# FPGA_IO.net
KiCad netlist of a schematic drawn in Altium Designer
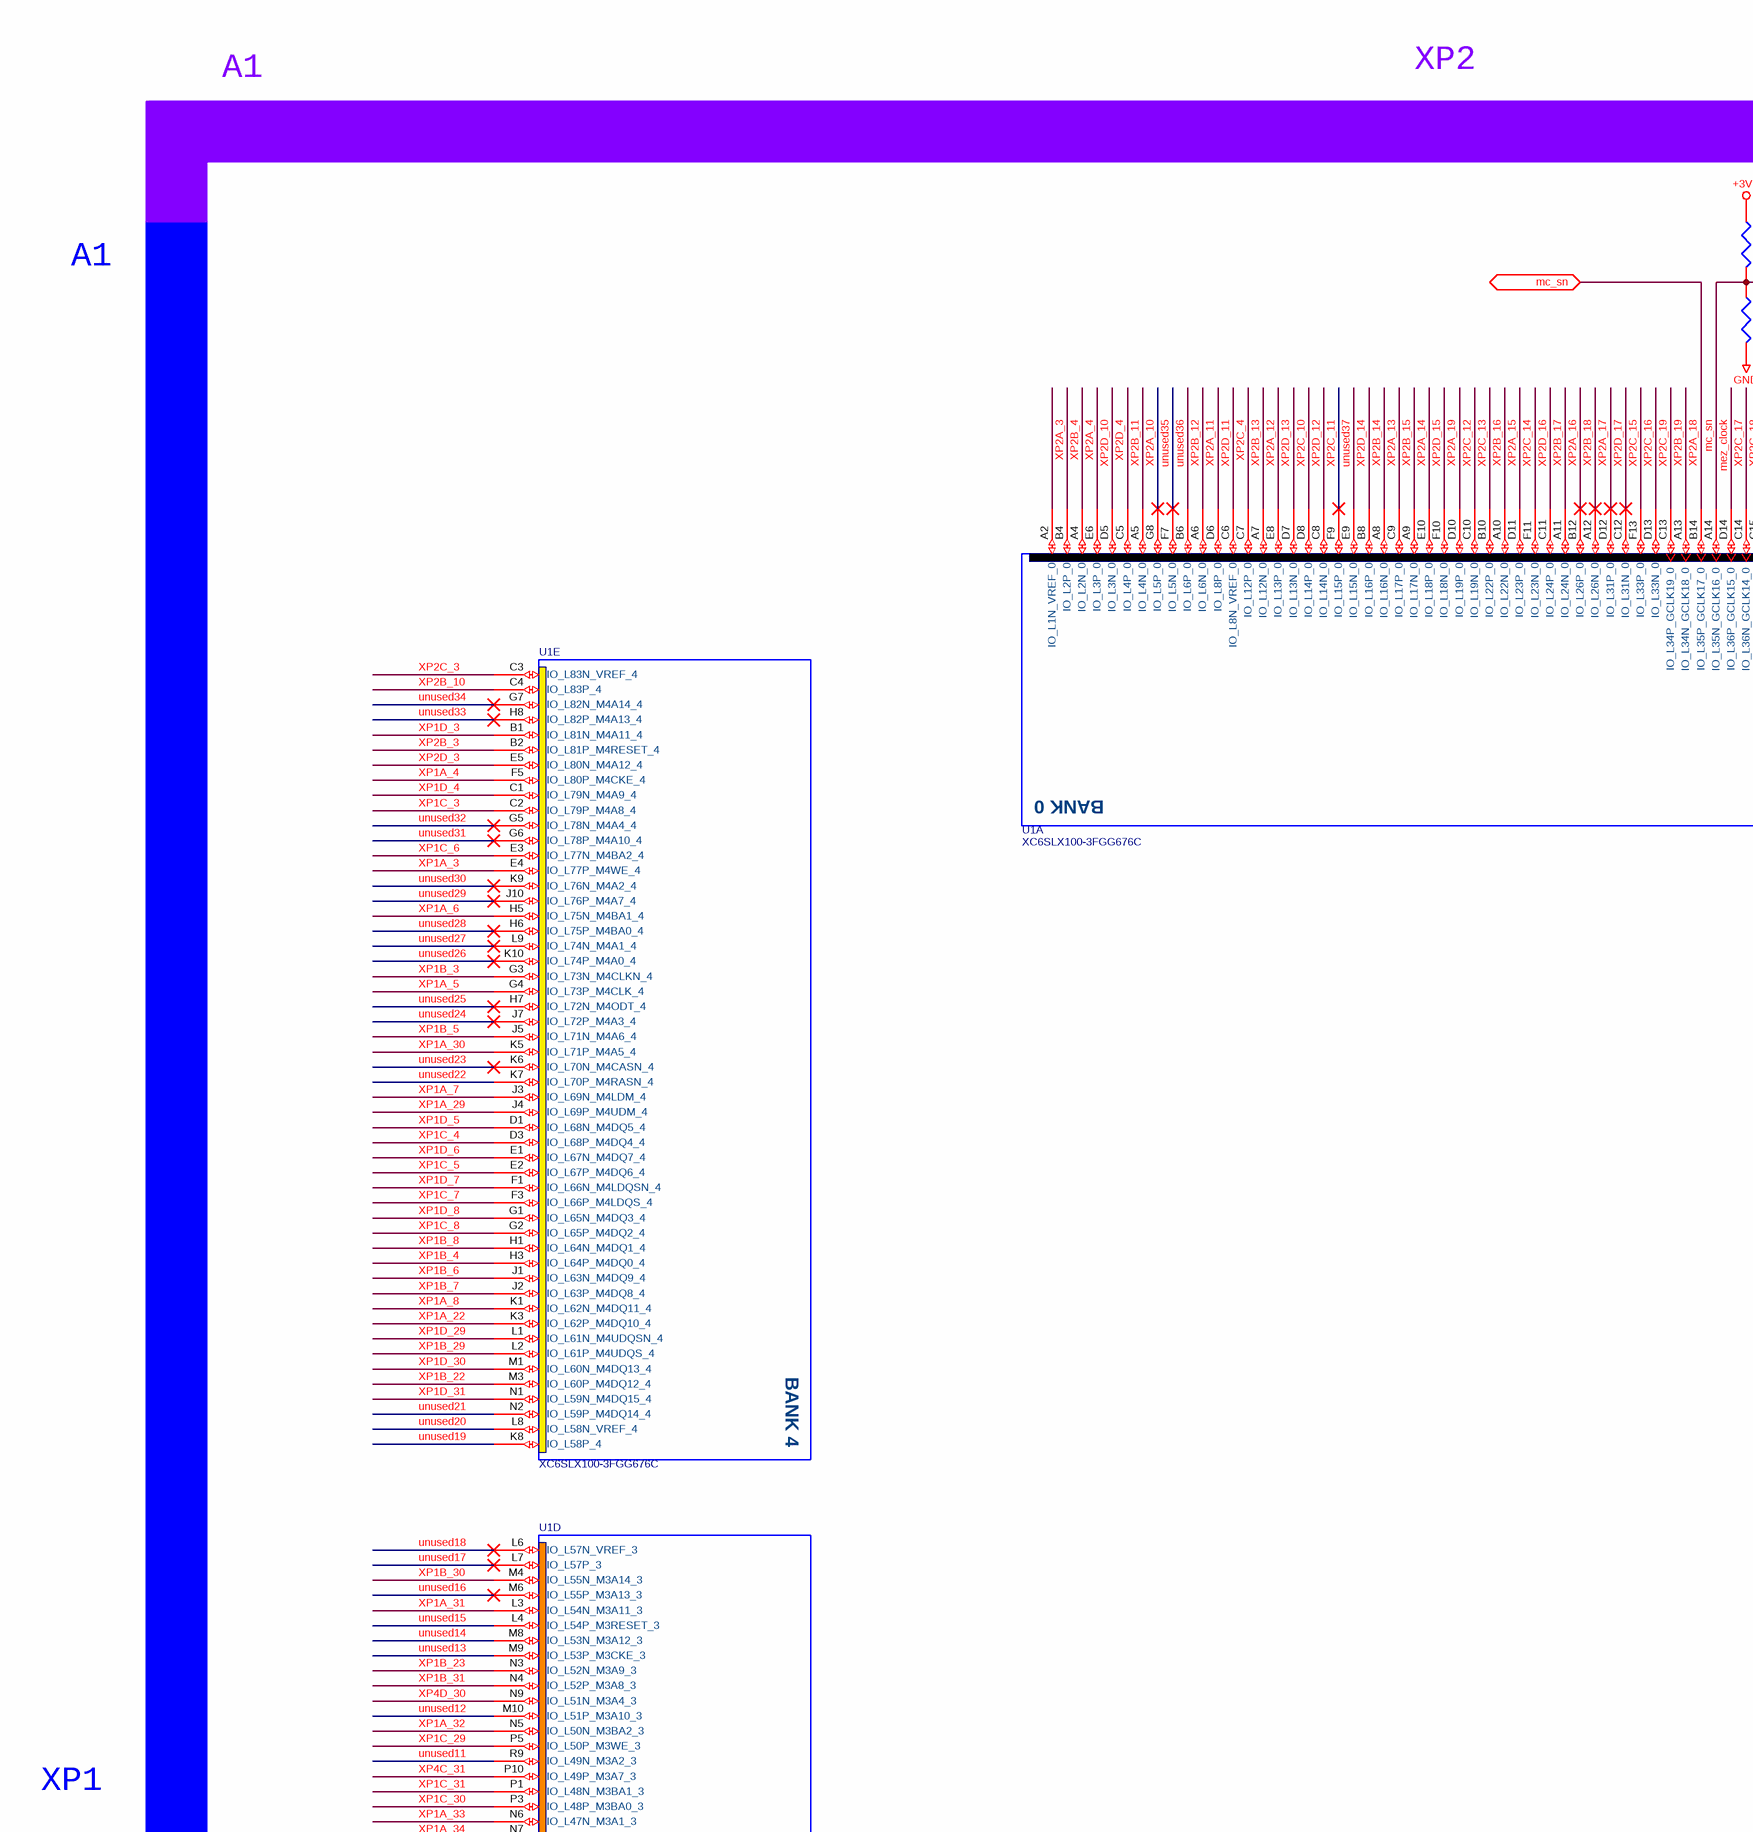
[diagram p0: FPGA_IO.SchDoc, top left]
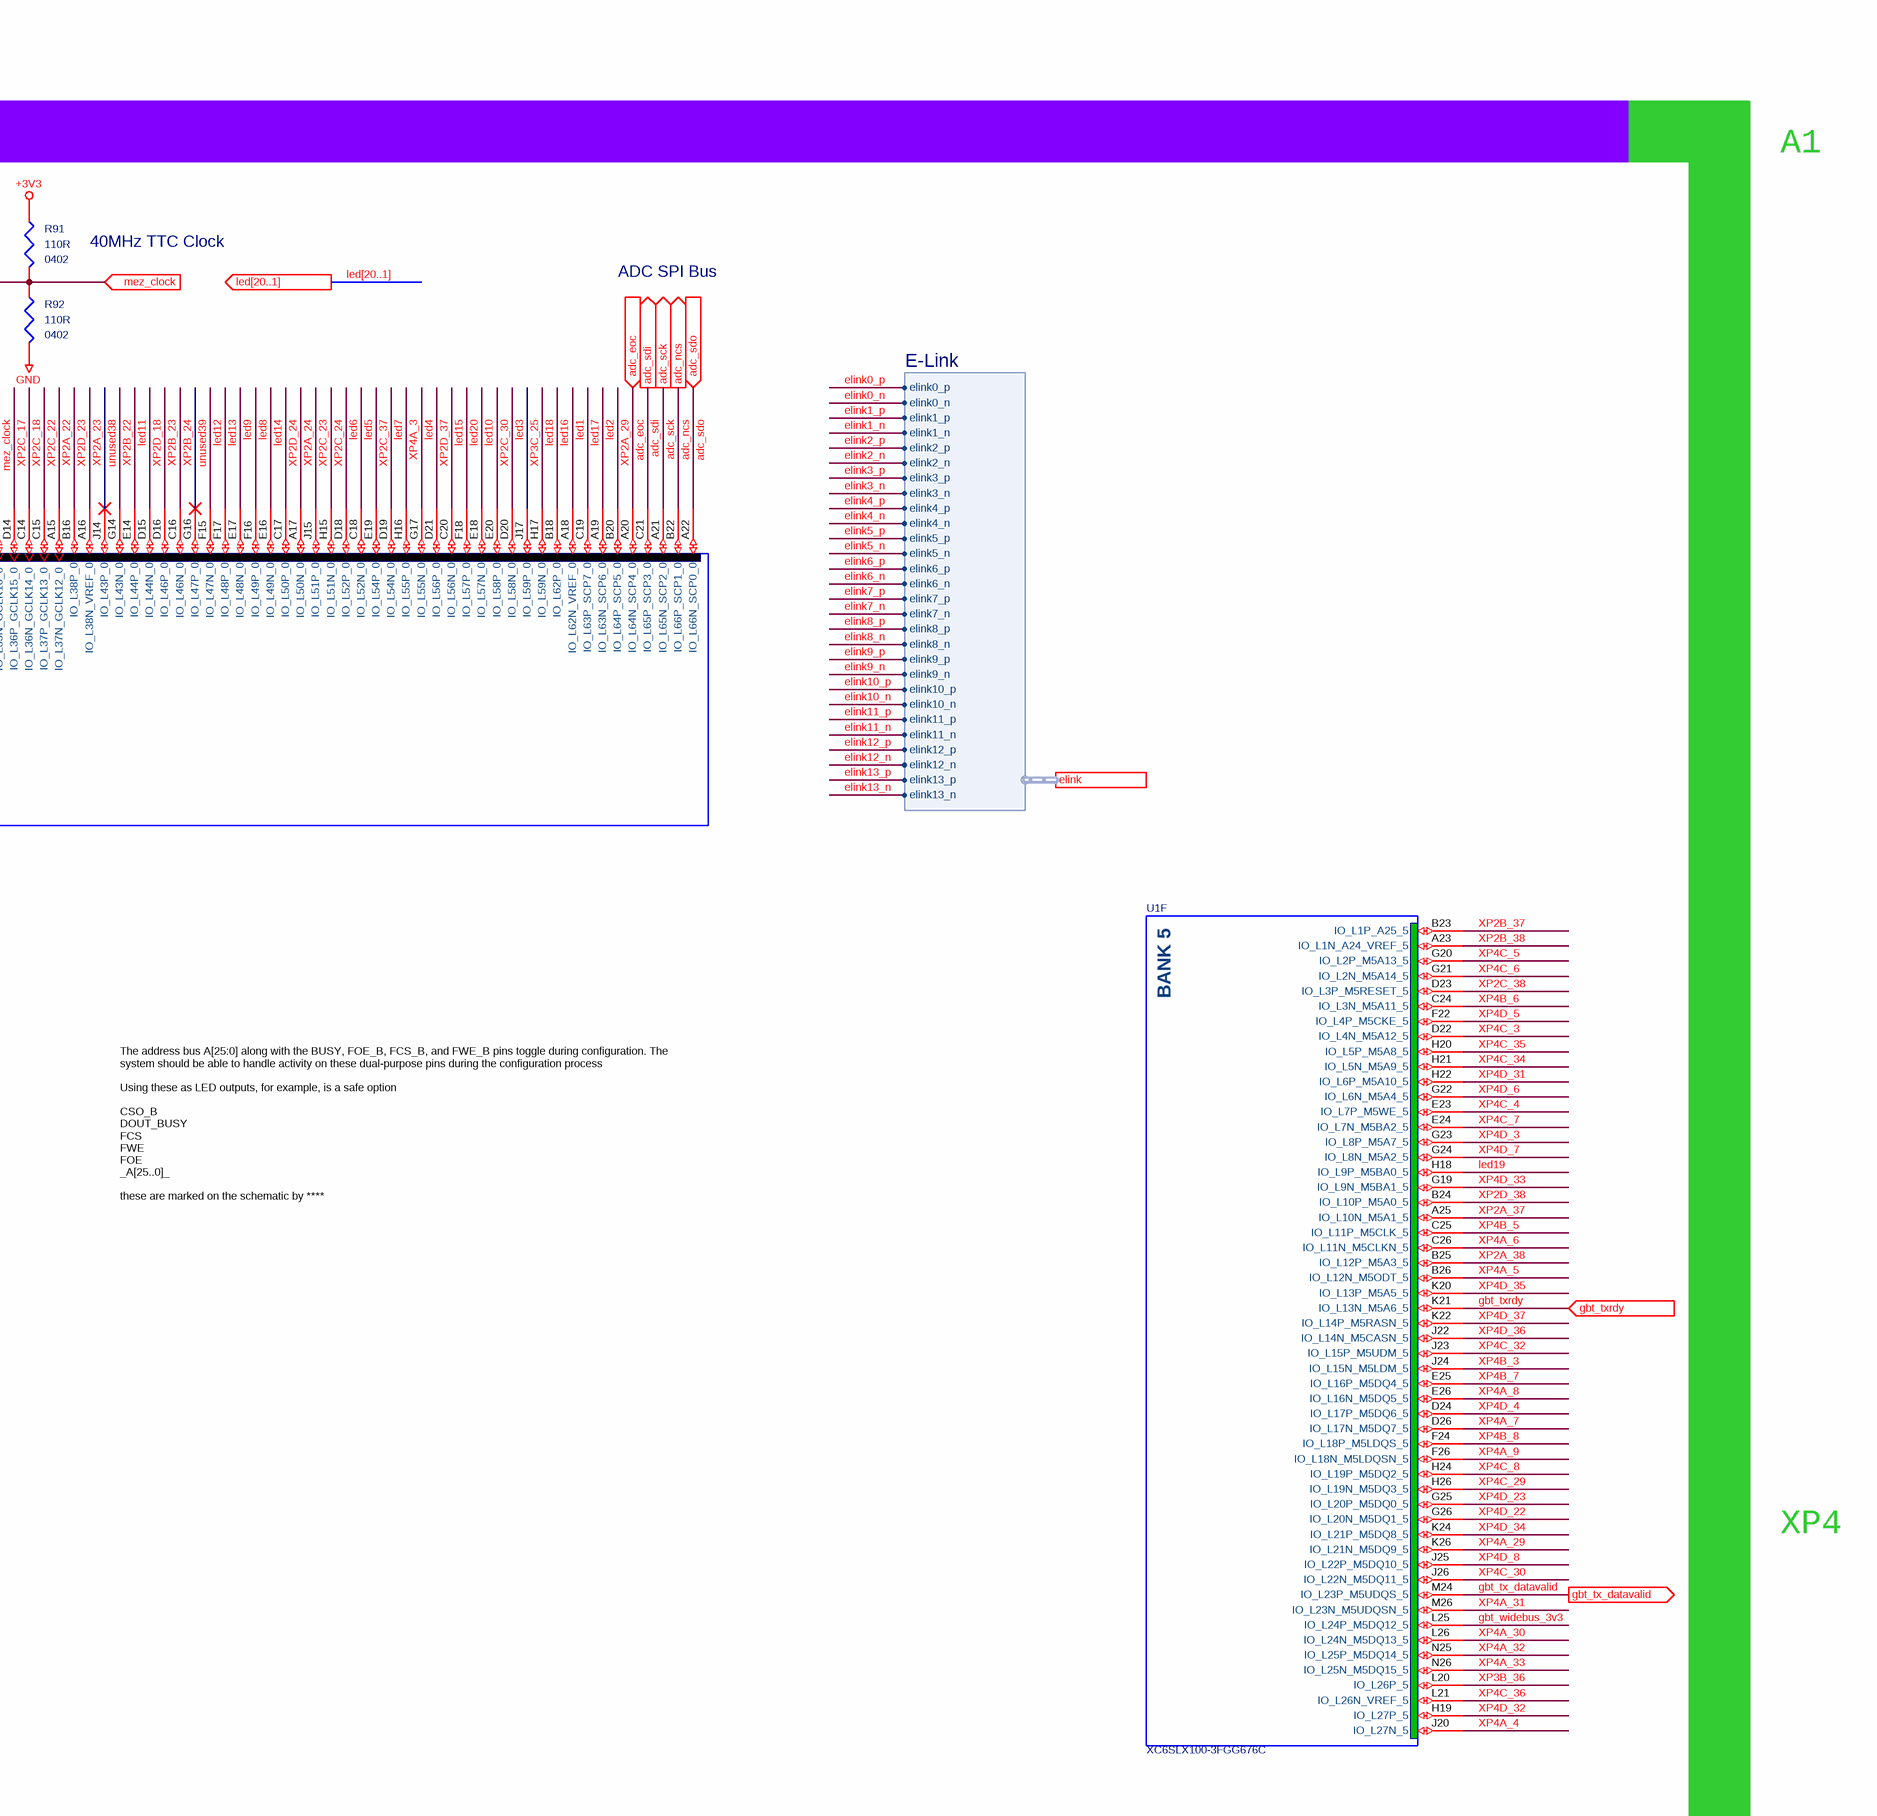
[diagram p1: FPGA_IO.SchDoc, top right]
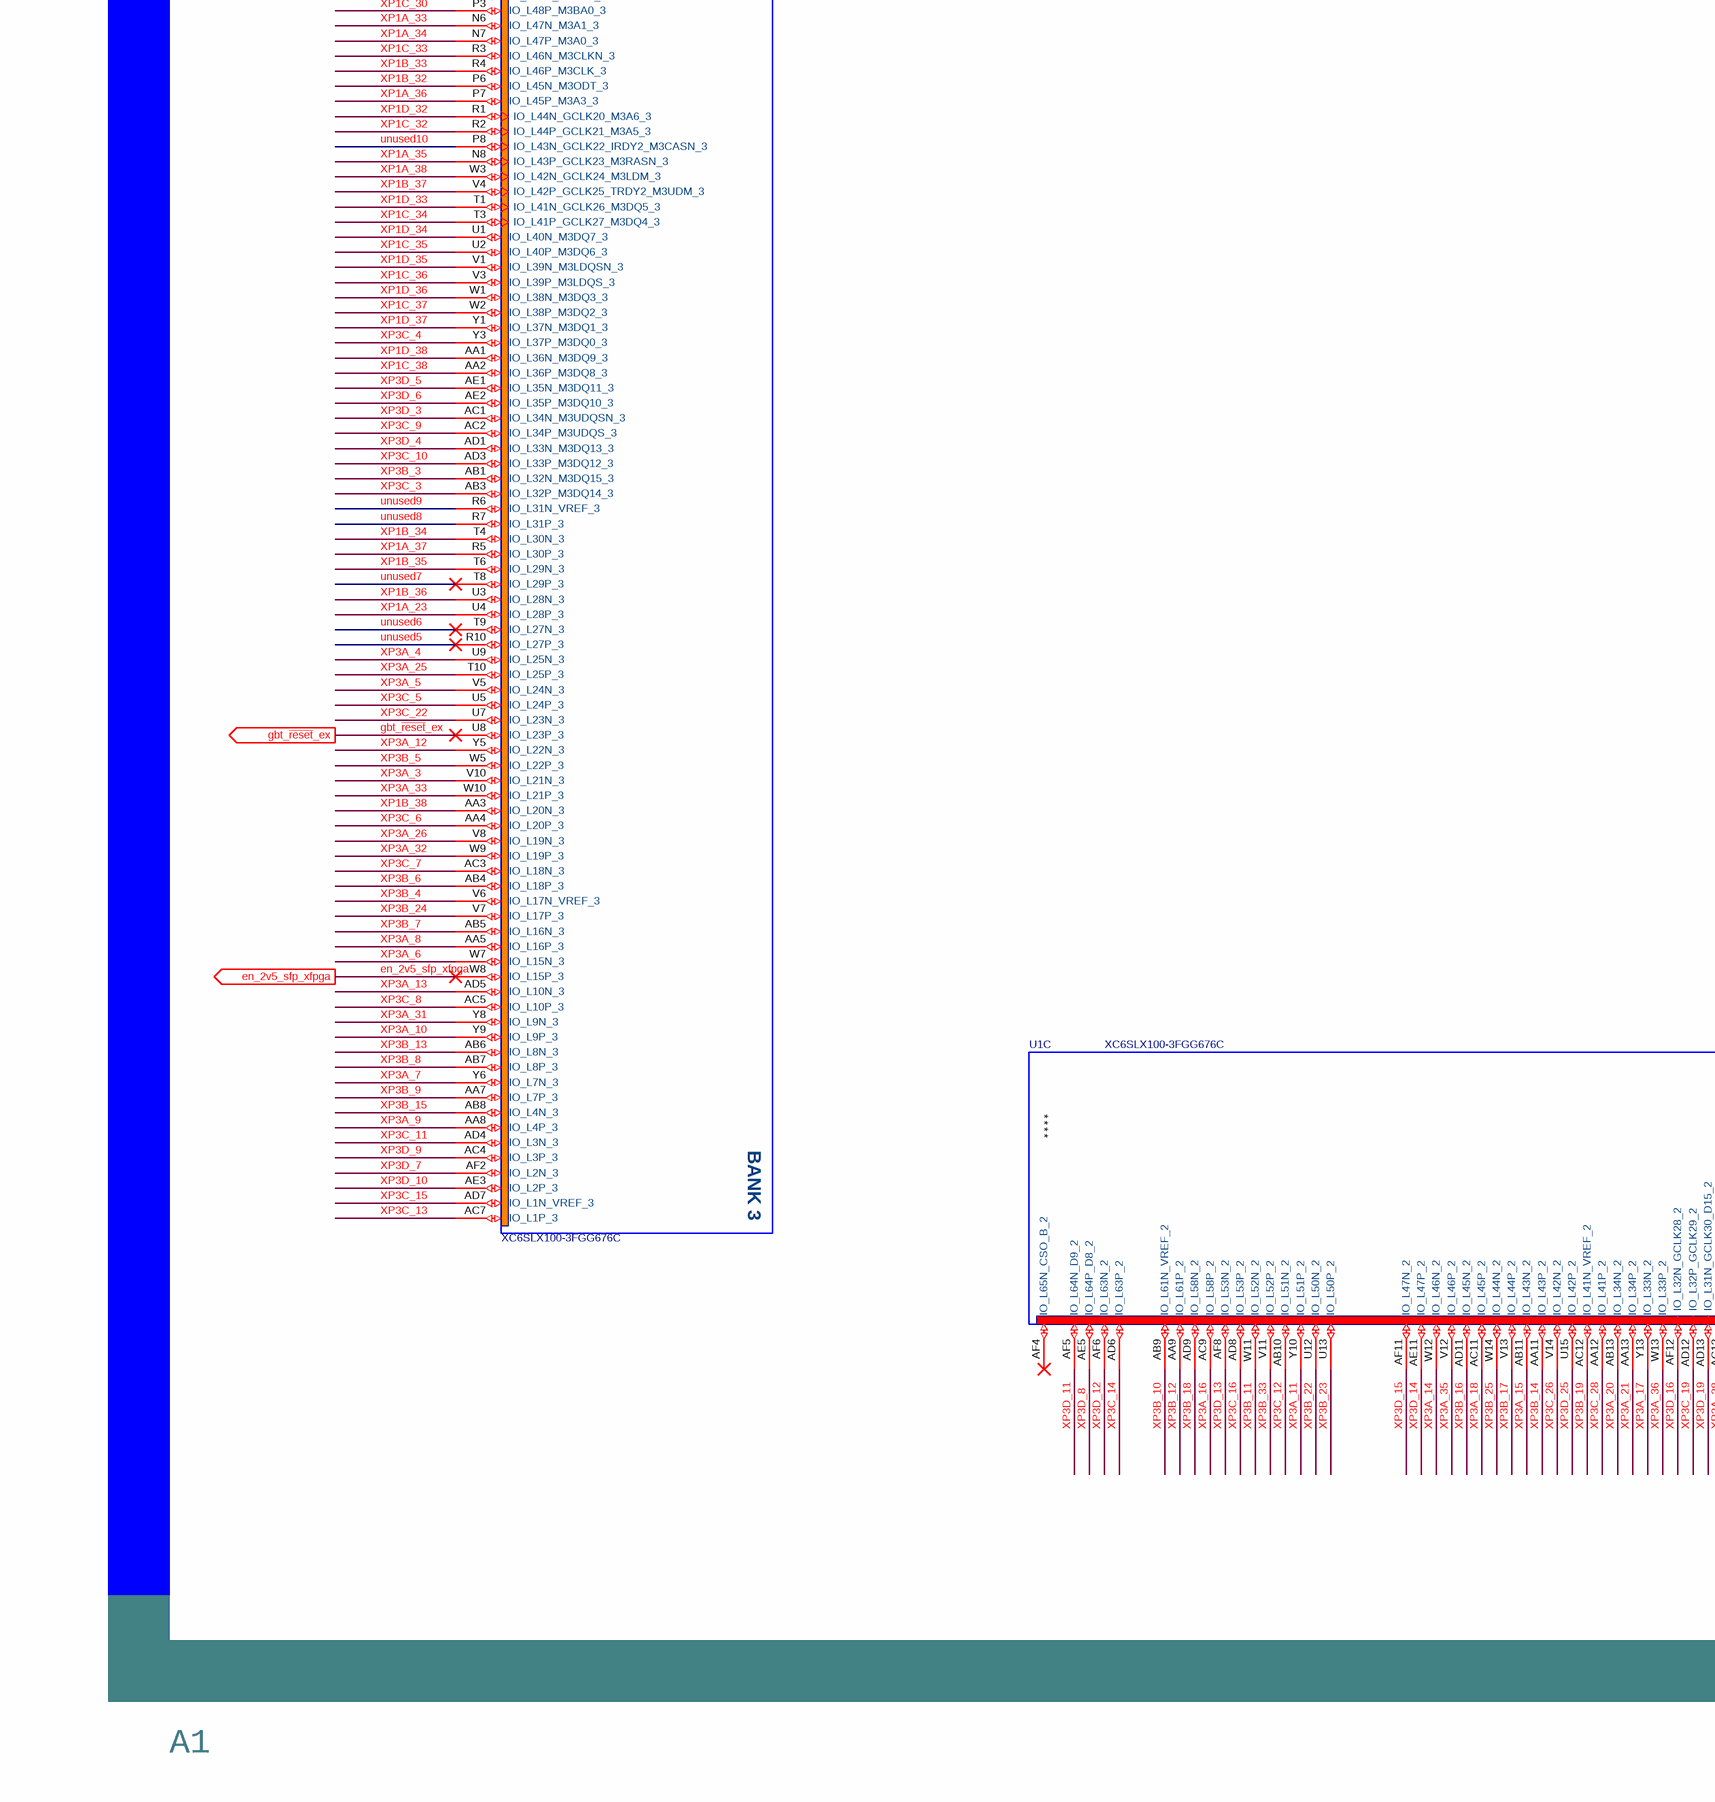
[diagram p2: FPGA_IO.SchDoc, bottom left]
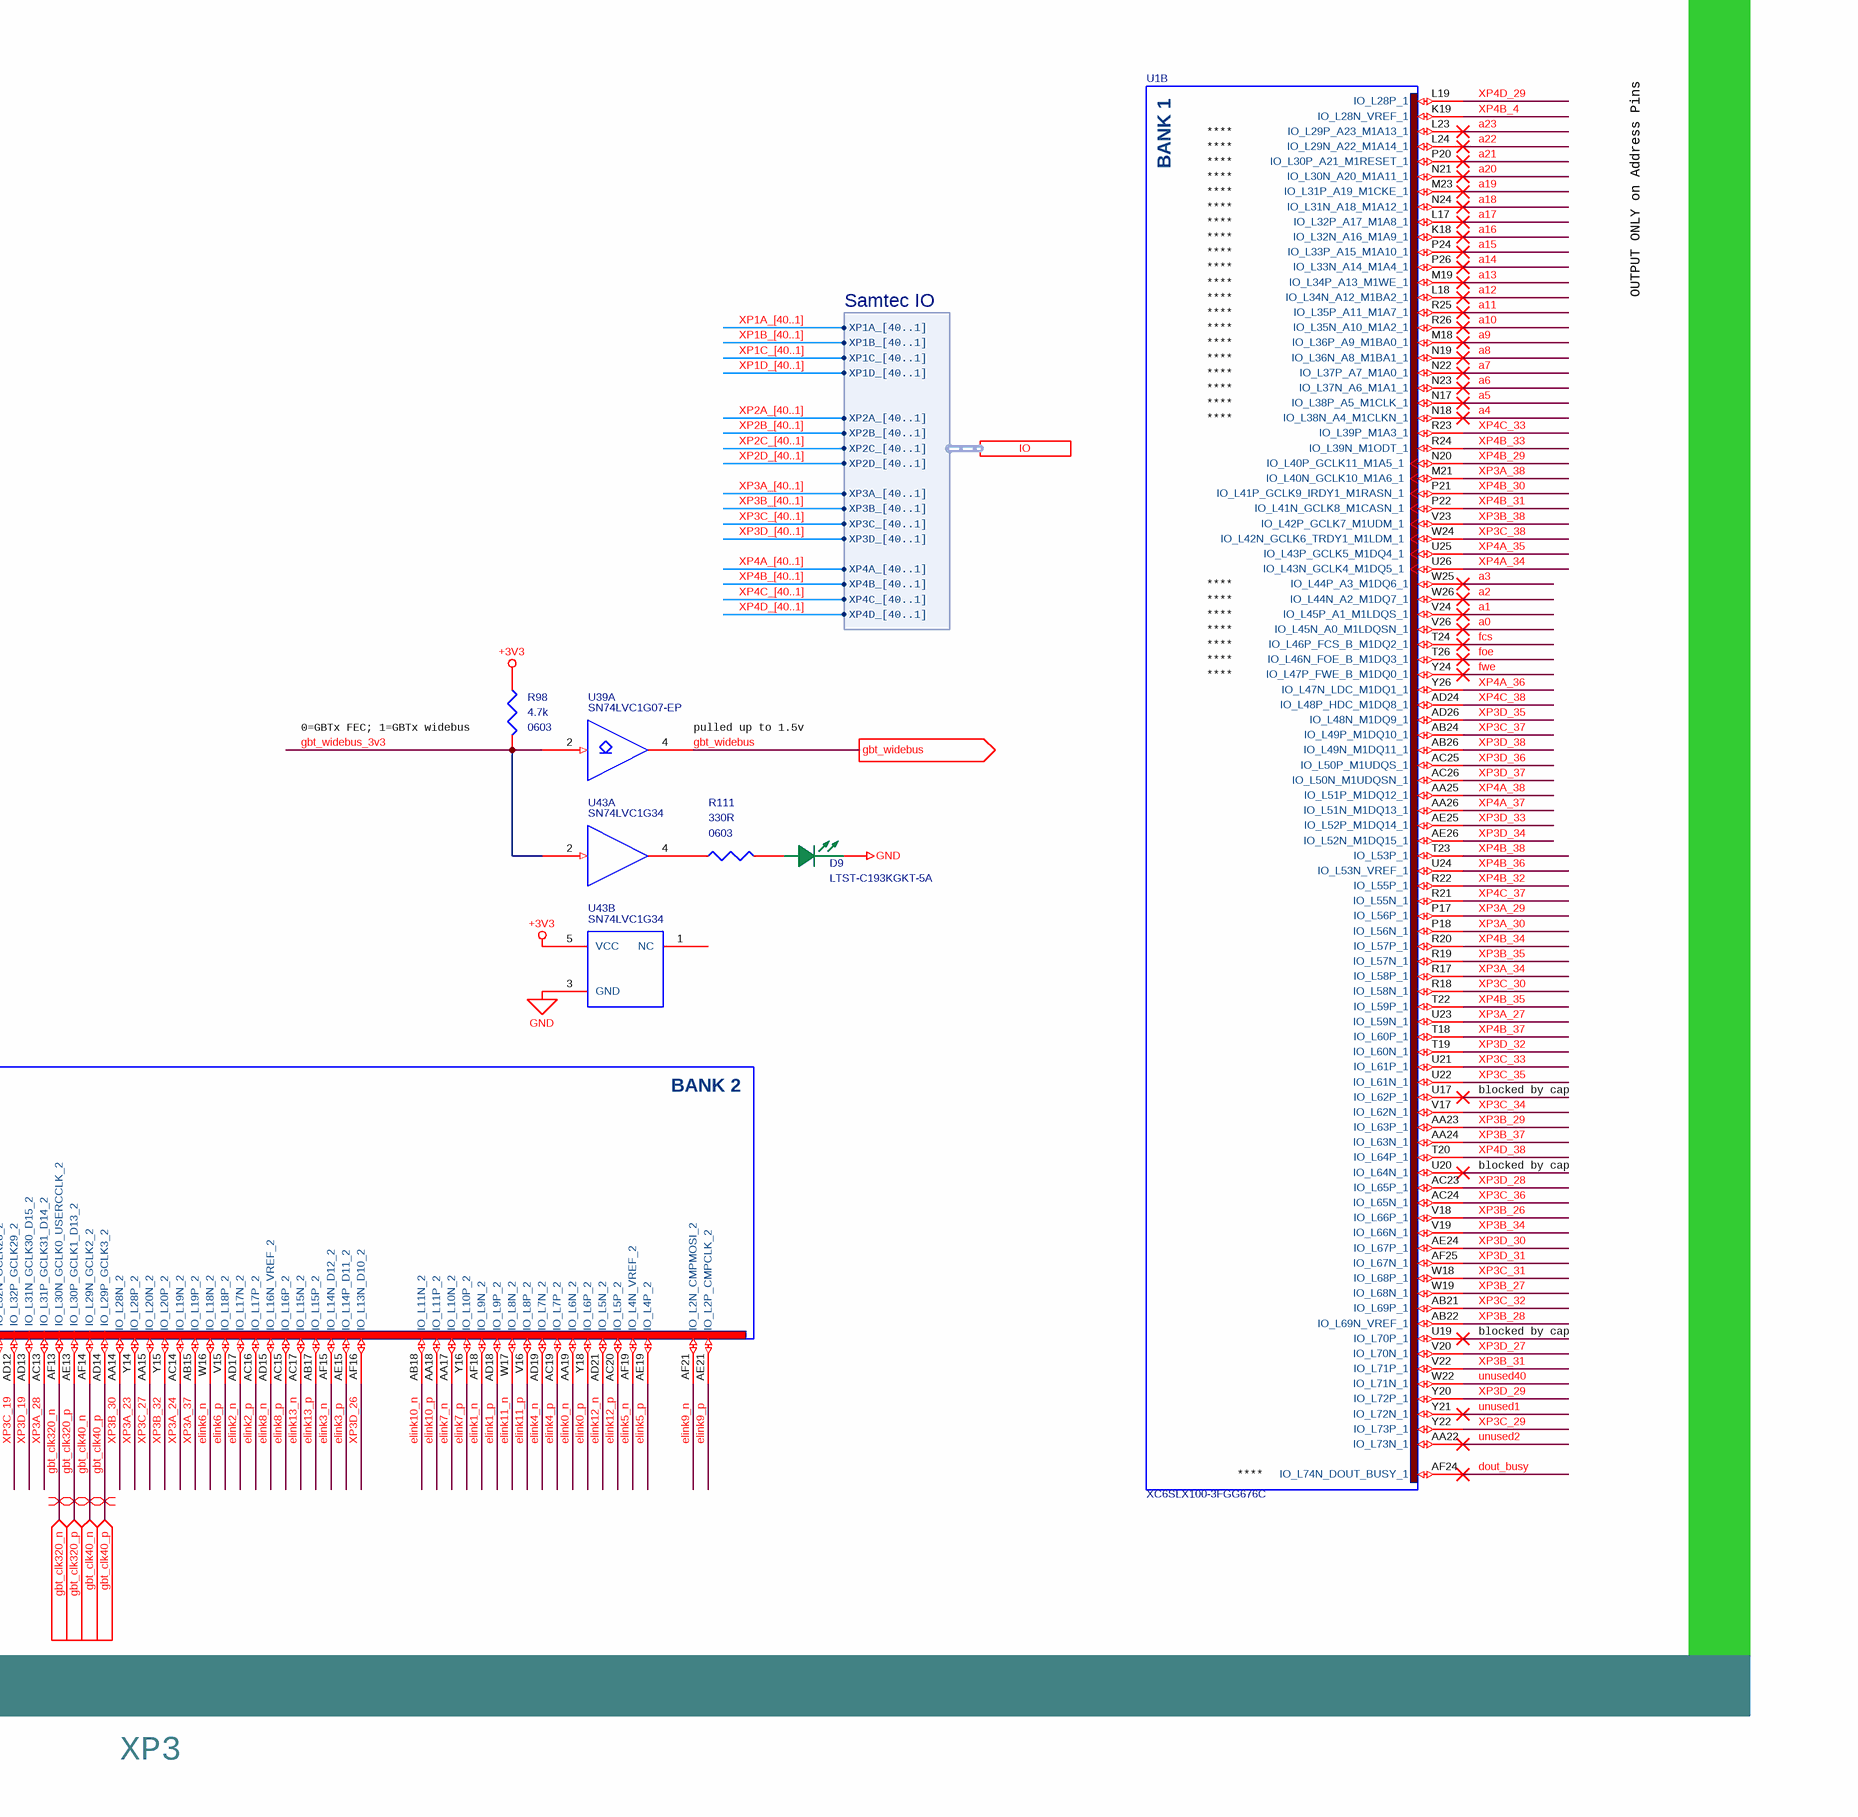
[diagram p3: FPGA_IO.SchDoc, bottom right]

(export (version "E")
  (design (tool "Eeschema 10.0.6"))
  (components
    (comp (ref "D9")
      (value "LTST-C193KGKT-5A")
      (footprint "MC_S6/SM/LED_0603")
      (description "LED GREEN CLEAR 0603 SMD")
      (fields (field (name "MANUFACTURER") "Lite-On Inc."))
      (libsource (lib "ALCT_MEZ_SPARTAN6_Library") (part "LTST-C193KGKT-5A"))
    )
    (comp (ref "R91")
      (value "110R")
      (footprint "MC_S6/SM/R_0402_IPC")
      (description "RES SMD 110 OHM 1% 1/10W 0402")
      (fields
        (field (name "MANUFACTURER") "Panasonic Electronic Components")
        (field (name "MANUFACTURER PART NUMBER") "ERJ-2RKF1100X")
        (field (name "SUPPLIER DEVICE PACKAGE") "0402")
      )
      (libsource (lib "ALCT_MEZ_SPARTAN6_Library") (part "ERJ-2RKF1100X"))
    )
    (comp (ref "R92")
      (value "110R")
      (footprint "MC_S6/SM/R_0402_IPC")
      (description "RES SMD 110 OHM 1% 1/10W 0402")
      (fields
        (field (name "MANUFACTURER") "Panasonic Electronic Components")
        (field (name "MANUFACTURER PART NUMBER") "ERJ-2RKF1100X")
        (field (name "SUPPLIER DEVICE PACKAGE") "0402")
      )
      (libsource (lib "ALCT_MEZ_SPARTAN6_Library") (part "ERJ-2RKF1100X"))
    )
    (comp (ref "R98")
      (value "4.7k")
      (footprint "MC_S6/SM/R_0603_IPC")
      (description "RES SMD 4.7K OHM 1% 1/10W 0603")
      (fields
        (field (name "TOLERANCE") "±1%")
        (field (name "MANUFACTURER") "Bourns Inc.")
        (field (name "SUPPLIER DEVICE PACKAGE") "0603")
      )
      (libsource (lib "ALCT_MEZ_SPARTAN6_Library") (part "CR0603-FX-4701ELF"))
    )
    (comp (ref "R111")
      (value "330R")
      (footprint "MC_S6/SM/R_0603_IPC")
      (description "RES SMD 330 OHM 1% 1/10W 0603")
      (fields
        (field (name "MANUFACTURER") "Bourns Inc.")
        (field (name "MANUFACTURER PART NUMBER") "CR0603-FX-3300ELF")
        (field (name "SUPPLIER DEVICE PACKAGE") "0603")
      )
      (libsource (lib "ALCT_MEZ_SPARTAN6_Library") (part "CR0603-FX-3300ELF"))
    )
    (comp (ref "U1")
      (value "XC6SLX100-3FGG676C")
      (footprint "FGG676")
      (fields (field (name "MANUFACTURER") "Xilinx Inc."))
      (libsource (lib "ALCT_MEZ_SPARTAN6_Library") (part "XC6SLX100-3FGG676C"))
    )
    (comp (ref "U39")
      (value "SN74LVC1G07-EP")
      (footprint "SOT353-1")
      (description "IC BUFF/DVR NON-INVERT Open Drain SC70-5")
      (fields
        (field (name "MANUFACTURER") "Texas Instruments")
        (field (name "MANUFACTURER PART NUMBER") "SN74LVC1G07MDCKREP")
      )
      (libsource (lib "ALCT_MEZ_SPARTAN6_Library") (part "SN74LVC1G07-EP"))
    )
    (comp (ref "U43")
      (value "SN74LVC1G34")
      (footprint "MC_S6/SM/SOT_553_DRL5")
      (description "IC BUFFER NON-INVERT SOT5")
      (fields
        (field (name "MANUFACTURER") "Texas Instruments")
        (field (name "MANUFACTURER PART NUMBER") "SN74LVC1G34DRLR")
      )
      (libsource (lib "ALCT_MEZ_SPARTAN6_Library") (part "SN74LVC1G34DRLR"))
    )
  )
  (nets
    (net (code "292") (name "+3V3") (class "Default")
      (node (ref "R91") (pin "1") (pinfunction "1_1") (pintype "passive"))
      (node (ref "R98") (pin "1") (pinfunction "1_1") (pintype "passive"))
      (node (ref "U43") (pin "5") (pinfunction "VCC_5") (pintype "power_in"))
    )
    (net (code "294") (name "/XP1A_3") (class "Default")
      (node (ref "U1") (pin "E4") (pinfunction "IO_L77P_M4WE_4_E4") (pintype "bidirectional"))
    )
    (net (code "295") (name "/XP1A_4") (class "Default")
      (node (ref "U1") (pin "F5") (pinfunction "IO_L80P_M4CKE_4_F5") (pintype "bidirectional"))
    )
    (net (code "296") (name "/XP1A_5") (class "Default")
      (node (ref "U1") (pin "G4") (pinfunction "IO_L73P_M4CLK_4_G4") (pintype "bidirectional"))
    )
    (net (code "297") (name "/XP1A_6") (class "Default")
      (node (ref "U1") (pin "H5") (pinfunction "IO_L75N_M4BA1_4_H5") (pintype "bidirectional"))
    )
    (net (code "298") (name "/XP1A_7") (class "Default")
      (node (ref "U1") (pin "J3") (pinfunction "IO_L69N_M4LDM_4_J3") (pintype "bidirectional"))
    )
    (net (code "299") (name "/XP1A_8") (class "Default")
      (node (ref "U1") (pin "K1") (pinfunction "IO_L62N_M4DQ11_4_K1") (pintype "bidirectional"))
    )
    (net (code "300") (name "/XP1A_22") (class "Default")
      (node (ref "U1") (pin "K3") (pinfunction "IO_L62P_M4DQ10_4_K3") (pintype "bidirectional"))
    )
    (net (code "301") (name "/XP1A_23") (class "Default")
      (node (ref "U1") (pin "U4") (pinfunction "IO_L28P_3_U4") (pintype "bidirectional"))
    )
    (net (code "302") (name "/XP1A_29") (class "Default")
      (node (ref "U1") (pin "J4") (pinfunction "IO_L69P_M4UDM_4_J4") (pintype "bidirectional"))
    )
    (net (code "303") (name "/XP1A_30") (class "Default")
      (node (ref "U1") (pin "K5") (pinfunction "IO_L71P_M4A5_4_K5") (pintype "bidirectional"))
    )
    (net (code "304") (name "/XP1A_31") (class "Default")
      (node (ref "U1") (pin "L3") (pinfunction "IO_L54N_M3A11_3_L3") (pintype "bidirectional"))
    )
    (net (code "305") (name "/XP1A_32") (class "Default")
      (node (ref "U1") (pin "N5") (pinfunction "IO_L50N_M3BA2_3_N5") (pintype "bidirectional"))
    )
    (net (code "306") (name "/XP1A_33") (class "Default")
      (node (ref "U1") (pin "N6") (pinfunction "IO_L47N_M3A1_3_N6") (pintype "bidirectional"))
    )
    (net (code "307") (name "/XP1A_34") (class "Default")
      (node (ref "U1") (pin "N7") (pinfunction "IO_L47P_M3A0_3_N7") (pintype "bidirectional"))
    )
    (net (code "308") (name "/XP1A_35") (class "Default")
      (node (ref "U1") (pin "N8") (pinfunction "IO_L43P_GCLK23_M3RASN_3_N8") (pintype "bidirectional"))
    )
    (net (code "309") (name "/XP1A_36") (class "Default")
      (node (ref "U1") (pin "P7") (pinfunction "IO_L45P_M3A3_3_P7") (pintype "bidirectional"))
    )
    (net (code "310") (name "/XP1A_37") (class "Default")
      (node (ref "U1") (pin "R5") (pinfunction "IO_L30P_3_R5") (pintype "bidirectional"))
    )
    (net (code "311") (name "/XP1A_38") (class "Default")
      (node (ref "U1") (pin "W3") (pinfunction "IO_L42N_GCLK24_M3LDM_3_W3") (pintype "bidirectional"))
    )
    (net (code "313") (name "/XP1B_3") (class "Default")
      (node (ref "U1") (pin "G3") (pinfunction "IO_L73N_M4CLKN_4_G3") (pintype "bidirectional"))
    )
    (net (code "314") (name "/XP1B_4") (class "Default")
      (node (ref "U1") (pin "H3") (pinfunction "IO_L64P_M4DQ0_4_H3") (pintype "bidirectional"))
    )
    (net (code "315") (name "/XP1B_5") (class "Default")
      (node (ref "U1") (pin "J5") (pinfunction "IO_L71N_M4A6_4_J5") (pintype "bidirectional"))
    )
    (net (code "316") (name "/XP1B_6") (class "Default")
      (node (ref "U1") (pin "J1") (pinfunction "IO_L63N_M4DQ9_4_J1") (pintype "bidirectional"))
    )
    (net (code "317") (name "/XP1B_7") (class "Default")
      (node (ref "U1") (pin "J2") (pinfunction "IO_L63P_M4DQ8_4_J2") (pintype "bidirectional"))
    )
    (net (code "318") (name "/XP1B_8") (class "Default")
      (node (ref "U1") (pin "H1") (pinfunction "IO_L64N_M4DQ1_4_H1") (pintype "bidirectional"))
    )
    (net (code "319") (name "/XP1B_22") (class "Default")
      (node (ref "U1") (pin "M3") (pinfunction "IO_L60P_M4DQ12_4_M3") (pintype "bidirectional"))
    )
    (net (code "320") (name "/XP1B_23") (class "Default")
      (node (ref "U1") (pin "N3") (pinfunction "IO_L52N_M3A9_3_N3") (pintype "bidirectional"))
    )
    (net (code "321") (name "/XP1B_29") (class "Default")
      (node (ref "U1") (pin "L2") (pinfunction "IO_L61P_M4UDQS_4_L2") (pintype "bidirectional"))
    )
    (net (code "322") (name "/XP1B_30") (class "Default")
      (node (ref "U1") (pin "M4") (pinfunction "IO_L55N_M3A14_3_M4") (pintype "bidirectional"))
    )
    (net (code "323") (name "/XP1B_31") (class "Default")
      (node (ref "U1") (pin "N4") (pinfunction "IO_L52P_M3A8_3_N4") (pintype "bidirectional"))
    )
    (net (code "324") (name "/XP1B_32") (class "Default")
      (node (ref "U1") (pin "P6") (pinfunction "IO_L45N_M3ODT_3_P6") (pintype "bidirectional"))
    )
    (net (code "325") (name "/XP1B_33") (class "Default")
      (node (ref "U1") (pin "R4") (pinfunction "IO_L46P_M3CLK_3_R4") (pintype "bidirectional"))
    )
    (net (code "326") (name "/XP1B_34") (class "Default")
      (node (ref "U1") (pin "T4") (pinfunction "IO_L30N_3_T4") (pintype "bidirectional"))
    )
    (net (code "327") (name "/XP1B_35") (class "Default")
      (node (ref "U1") (pin "T6") (pinfunction "IO_L29N_3_T6") (pintype "bidirectional"))
    )
    (net (code "328") (name "/XP1B_36") (class "Default")
      (node (ref "U1") (pin "U3") (pinfunction "IO_L28N_3_U3") (pintype "bidirectional"))
    )
    (net (code "329") (name "/XP1B_37") (class "Default")
      (node (ref "U1") (pin "V4") (pinfunction "IO_L42P_GCLK25_TRDY2_M3UDM_3_V4") (pintype "bidirectional"))
    )
    (net (code "330") (name "/XP1B_38") (class "Default")
      (node (ref "U1") (pin "AA3") (pinfunction "IO_L20N_3_AA3") (pintype "bidirectional"))
    )
    (net (code "332") (name "/XP1C_3") (class "Default")
      (node (ref "U1") (pin "C2") (pinfunction "IO_L79P_M4A8_4_C2") (pintype "bidirectional"))
    )
    (net (code "333") (name "/XP1C_4") (class "Default")
      (node (ref "U1") (pin "D3") (pinfunction "IO_L68P_M4DQ4_4_D3") (pintype "bidirectional"))
    )
    (net (code "334") (name "/XP1C_5") (class "Default")
      (node (ref "U1") (pin "E2") (pinfunction "IO_L67P_M4DQ6_4_E2") (pintype "bidirectional"))
    )
    (net (code "335") (name "/XP1C_6") (class "Default")
      (node (ref "U1") (pin "E3") (pinfunction "IO_L77N_M4BA2_4_E3") (pintype "bidirectional"))
    )
    (net (code "336") (name "/XP1C_7") (class "Default")
      (node (ref "U1") (pin "F3") (pinfunction "IO_L66P_M4LDQS_4_F3") (pintype "bidirectional"))
    )
    (net (code "337") (name "/XP1C_8") (class "Default")
      (node (ref "U1") (pin "G2") (pinfunction "IO_L65P_M4DQ2_4_G2") (pintype "bidirectional"))
    )
    (net (code "338") (name "/XP1C_29") (class "Default")
      (node (ref "U1") (pin "P5") (pinfunction "IO_L50P_M3WE_3_P5") (pintype "bidirectional"))
    )
    (net (code "339") (name "/XP1C_30") (class "Default")
      (node (ref "U1") (pin "P3") (pinfunction "IO_L48P_M3BA0_3_P3") (pintype "bidirectional"))
    )
    (net (code "340") (name "/XP1C_31") (class "Default")
      (node (ref "U1") (pin "P1") (pinfunction "IO_L48N_M3BA1_3_P1") (pintype "bidirectional"))
    )
    (net (code "341") (name "/XP1C_32") (class "Default")
      (node (ref "U1") (pin "R2") (pinfunction "IO_L44P_GCLK21_M3A5_3_R2") (pintype "bidirectional"))
    )
    (net (code "342") (name "/XP1C_33") (class "Default")
      (node (ref "U1") (pin "R3") (pinfunction "IO_L46N_M3CLKN_3_R3") (pintype "bidirectional"))
    )
    (net (code "343") (name "/XP1C_34") (class "Default")
      (node (ref "U1") (pin "T3") (pinfunction "IO_L41P_GCLK27_M3DQ4_3_T3") (pintype "bidirectional"))
    )
    (net (code "344") (name "/XP1C_35") (class "Default")
      (node (ref "U1") (pin "U2") (pinfunction "IO_L40P_M3DQ6_3_U2") (pintype "bidirectional"))
    )
    (net (code "345") (name "/XP1C_36") (class "Default")
      (node (ref "U1") (pin "V3") (pinfunction "IO_L39P_M3LDQS_3_V3") (pintype "bidirectional"))
    )
    (net (code "346") (name "/XP1C_37") (class "Default")
      (node (ref "U1") (pin "W2") (pinfunction "IO_L38P_M3DQ2_3_W2") (pintype "bidirectional"))
    )
    (net (code "347") (name "/XP1C_38") (class "Default")
      (node (ref "U1") (pin "AA2") (pinfunction "IO_L36P_M3DQ8_3_AA2") (pintype "bidirectional"))
    )
    (net (code "349") (name "/XP1D_3") (class "Default")
      (node (ref "U1") (pin "B1") (pinfunction "IO_L81N_M4A11_4_B1") (pintype "bidirectional"))
    )
    (net (code "350") (name "/XP1D_4") (class "Default")
      (node (ref "U1") (pin "C1") (pinfunction "IO_L79N_M4A9_4_C1") (pintype "bidirectional"))
    )
    (net (code "351") (name "/XP1D_5") (class "Default")
      (node (ref "U1") (pin "D1") (pinfunction "IO_L68N_M4DQ5_4_D1") (pintype "bidirectional"))
    )
    (net (code "352") (name "/XP1D_6") (class "Default")
      (node (ref "U1") (pin "E1") (pinfunction "IO_L67N_M4DQ7_4_E1") (pintype "bidirectional"))
    )
    (net (code "353") (name "/XP1D_7") (class "Default")
      (node (ref "U1") (pin "F1") (pinfunction "IO_L66N_M4LDQSN_4_F1") (pintype "bidirectional"))
    )
    (net (code "354") (name "/XP1D_8") (class "Default")
      (node (ref "U1") (pin "G1") (pinfunction "IO_L65N_M4DQ3_4_G1") (pintype "bidirectional"))
    )
    (net (code "355") (name "/XP1D_29") (class "Default")
      (node (ref "U1") (pin "L1") (pinfunction "IO_L61N_M4UDQSN_4_L1") (pintype "bidirectional"))
    )
    (net (code "356") (name "/XP1D_30") (class "Default")
      (node (ref "U1") (pin "M1") (pinfunction "IO_L60N_M4DQ13_4_M1") (pintype "bidirectional"))
    )
    (net (code "357") (name "/XP1D_31") (class "Default")
      (node (ref "U1") (pin "N1") (pinfunction "IO_L59N_M4DQ15_4_N1") (pintype "bidirectional"))
    )
    (net (code "358") (name "/XP1D_32") (class "Default")
      (node (ref "U1") (pin "R1") (pinfunction "IO_L44N_GCLK20_M3A6_3_R1") (pintype "bidirectional"))
    )
    (net (code "359") (name "/XP1D_33") (class "Default")
      (node (ref "U1") (pin "T1") (pinfunction "IO_L41N_GCLK26_M3DQ5_3_T1") (pintype "bidirectional"))
    )
    (net (code "360") (name "/XP1D_34") (class "Default")
      (node (ref "U1") (pin "U1") (pinfunction "IO_L40N_M3DQ7_3_U1") (pintype "bidirectional"))
    )
    (net (code "361") (name "/XP1D_35") (class "Default")
      (node (ref "U1") (pin "V1") (pinfunction "IO_L39N_M3LDQSN_3_V1") (pintype "bidirectional"))
    )
    (net (code "362") (name "/XP1D_36") (class "Default")
      (node (ref "U1") (pin "W1") (pinfunction "IO_L38N_M3DQ3_3_W1") (pintype "bidirectional"))
    )
    (net (code "363") (name "/XP1D_37") (class "Default")
      (node (ref "U1") (pin "Y1") (pinfunction "IO_L37N_M3DQ1_3_Y1") (pintype "bidirectional"))
    )
    (net (code "364") (name "/XP1D_38") (class "Default")
      (node (ref "U1") (pin "AA1") (pinfunction "IO_L36N_M3DQ9_3_AA1") (pintype "bidirectional"))
    )
    (net (code "366") (name "/XP2A_3") (class "Default")
      (node (ref "U1") (pin "A2") (pinfunction "IO_L1N_VREF_0_A2") (pintype "bidirectional"))
    )
    (net (code "367") (name "/XP2A_4") (class "Default")
      (node (ref "U1") (pin "A4") (pinfunction "IO_L2N_0_A4") (pintype "bidirectional"))
    )
    (net (code "368") (name "/XP2A_10") (class "Default")
      (node (ref "U1") (pin "A5") (pinfunction "IO_L4N_0_A5") (pintype "bidirectional"))
    )
    (net (code "369") (name "/XP2A_11") (class "Default")
      (node (ref "U1") (pin "A6") (pinfunction "IO_L6N_0_A6") (pintype "bidirectional"))
    )
    (net (code "370") (name "/XP2A_12") (class "Default")
      (node (ref "U1") (pin "A7") (pinfunction "IO_L12N_0_A7") (pintype "bidirectional"))
    )
    (net (code "371") (name "/XP2A_13") (class "Default")
      (node (ref "U1") (pin "A8") (pinfunction "IO_L16N_0_A8") (pintype "bidirectional"))
    )
    (net (code "372") (name "/XP2A_14") (class "Default")
      (node (ref "U1") (pin "A9") (pinfunction "IO_L17N_0_A9") (pintype "bidirectional"))
    )
    (net (code "373") (name "/XP2A_15") (class "Default")
      (node (ref "U1") (pin "A10") (pinfunction "IO_L22N_0_A10") (pintype "bidirectional"))
    )
    (net (code "374") (name "/XP2A_16") (class "Default")
      (node (ref "U1") (pin "A11") (pinfunction "IO_L24N_0_A11") (pintype "bidirectional"))
    )
    (net (code "375") (name "/XP2A_17") (class "Default")
      (node (ref "U1") (pin "A12") (pinfunction "IO_L26N_0_A12") (pintype "bidirectional+no_connect"))
    )
    (net (code "376") (name "/XP2A_18") (class "Default")
      (node (ref "U1") (pin "A13") (pinfunction "IO_L34N_GCLK18_0_A13") (pintype "bidirectional"))
    )
    (net (code "377") (name "/XP2A_19") (class "Default")
      (node (ref "U1") (pin "F10") (pinfunction "IO_L18N_0_F10") (pintype "bidirectional"))
    )
    (net (code "378") (name "/XP2A_22") (class "Default")
      (node (ref "U1") (pin "A15") (pinfunction "IO_L37N_GCLK12_0_A15") (pintype "bidirectional"))
    )
    (net (code "379") (name "/XP2A_23") (class "Default")
      (node (ref "U1") (pin "A16") (pinfunction "IO_L38N_VREF_0_A16") (pintype "bidirectional"))
    )
    (net (code "380") (name "/XP2A_24") (class "Default")
      (node (ref "U1") (pin "A17") (pinfunction "IO_L50N_0_A17") (pintype "bidirectional"))
    )
    (net (code "381") (name "/XP2A_29") (class "Default")
      (node (ref "U1") (pin "B20") (pinfunction "IO_L64P_SCP5_0_B20") (pintype "bidirectional"))
    )
    (net (code "382") (name "/XP2A_37") (class "Default")
      (node (ref "U1") (pin "A25") (pinfunction "IO_L10N_M5A1_5_A25") (pintype "bidirectional"))
    )
    (net (code "383") (name "/XP2A_38") (class "Default")
      (node (ref "U1") (pin "B25") (pinfunction "IO_L12P_M5A3_5_B25") (pintype "bidirectional"))
    )
    (net (code "385") (name "/XP2B_3") (class "Default")
      (node (ref "U1") (pin "B2") (pinfunction "IO_L81P_M4RESET_4_B2") (pintype "bidirectional"))
    )
    (net (code "386") (name "/XP2B_4") (class "Default")
      (node (ref "U1") (pin "B4") (pinfunction "IO_L2P_0_B4") (pintype "bidirectional"))
    )
    (net (code "387") (name "/XP2B_10") (class "Default")
      (node (ref "U1") (pin "C4") (pinfunction "IO_L83P_4_C4") (pintype "bidirectional"))
    )
    (net (code "388") (name "/XP2B_11") (class "Default")
      (node (ref "U1") (pin "C5") (pinfunction "IO_L4P_0_C5") (pintype "bidirectional"))
    )
    (net (code "389") (name "/XP2B_12") (class "Default")
      (node (ref "U1") (pin "B6") (pinfunction "IO_L6P_0_B6") (pintype "bidirectional"))
    )
    (net (code "390") (name "/XP2B_13") (class "Default")
      (node (ref "U1") (pin "C7") (pinfunction "IO_L12P_0_C7") (pintype "bidirectional"))
    )
    (net (code "391") (name "/XP2B_14") (class "Default")
      (node (ref "U1") (pin "B8") (pinfunction "IO_L16P_0_B8") (pintype "bidirectional"))
    )
    (net (code "392") (name "/XP2B_15") (class "Default")
      (node (ref "U1") (pin "C9") (pinfunction "IO_L17P_0_C9") (pintype "bidirectional"))
    )
    (net (code "393") (name "/XP2B_16") (class "Default")
      (node (ref "U1") (pin "B10") (pinfunction "IO_L22P_0_B10") (pintype "bidirectional"))
    )
    (net (code "394") (name "/XP2B_17") (class "Default")
      (node (ref "U1") (pin "C11") (pinfunction "IO_L24P_0_C11") (pintype "bidirectional"))
    )
    (net (code "395") (name "/XP2B_18") (class "Default")
      (node (ref "U1") (pin "B12") (pinfunction "IO_L26P_0_B12") (pintype "bidirectional+no_connect"))
    )
    (net (code "396") (name "/XP2B_19") (class "Default")
      (node (ref "U1") (pin "C13") (pinfunction "IO_L34P_GCLK19_0_C13") (pintype "bidirectional"))
    )
    (net (code "397") (name "/XP2B_22") (class "Default")
      (node (ref "U1") (pin "G14") (pinfunction "IO_L43N_0_G14") (pintype "bidirectional"))
    )
    (net (code "398") (name "/XP2B_23") (class "Default")
      (node (ref "U1") (pin "D16") (pinfunction "IO_L46P_0_D16") (pintype "bidirectional"))
    )
    (net (code "399") (name "/XP2B_24") (class "Default")
      (node (ref "U1") (pin "C16") (pinfunction "IO_L46N_0_C16") (pintype "bidirectional"))
    )
    (net (code "400") (name "/XP2B_37") (class "Default")
      (node (ref "U1") (pin "B23") (pinfunction "IO_L1P_A25_5_B23") (pintype "bidirectional"))
    )
    (net (code "401") (name "/XP2B_38") (class "Default")
      (node (ref "U1") (pin "A23") (pinfunction "IO_L1N_A24_VREF_5_A23") (pintype "bidirectional"))
    )
    (net (code "403") (name "/XP2C_3") (class "Default")
      (node (ref "U1") (pin "C3") (pinfunction "IO_L83N_VREF_4_C3") (pintype "bidirectional"))
    )
    (net (code "404") (name "/XP2C_4") (class "Default")
      (node (ref "U1") (pin "C6") (pinfunction "IO_L8N_VREF_0_C6") (pintype "bidirectional"))
    )
    (net (code "405") (name "/XP2C_10") (class "Default")
      (node (ref "U1") (pin "D7") (pinfunction "IO_L13N_0_D7") (pintype "bidirectional"))
    )
    (net (code "406") (name "/XP2C_11") (class "Default")
      (node (ref "U1") (pin "C8") (pinfunction "IO_L14N_0_C8") (pintype "bidirectional"))
    )
    (net (code "407") (name "/XP2C_12") (class "Default")
      (node (ref "U1") (pin "D10") (pinfunction "IO_L19P_0_D10") (pintype "bidirectional"))
    )
    (net (code "408") (name "/XP2C_13") (class "Default")
      (node (ref "U1") (pin "C10") (pinfunction "IO_L19N_0_C10") (pintype "bidirectional"))
    )
    (net (code "409") (name "/XP2C_14") (class "Default")
      (node (ref "U1") (pin "D11") (pinfunction "IO_L23P_0_D11") (pintype "bidirectional"))
    )
    (net (code "410") (name "/XP2C_15") (class "Default")
      (node (ref "U1") (pin "C12") (pinfunction "IO_L31N_0_C12") (pintype "bidirectional+no_connect"))
    )
    (net (code "411") (name "/XP2C_16") (class "Default")
      (node (ref "U1") (pin "F13") (pinfunction "IO_L33P_0_F13") (pintype "bidirectional"))
    )
    (net (code "412") (name "/XP2C_17") (class "Default")
      (node (ref "U1") (pin "D14") (pinfunction "IO_L36P_GCLK15_0_D14") (pintype "bidirectional"))
    )
    (net (code "413") (name "/XP2C_18") (class "Default")
      (node (ref "U1") (pin "C14") (pinfunction "IO_L36N_GCLK14_0_C14") (pintype "bidirectional"))
    )
    (net (code "414") (name "/XP2C_19") (class "Default")
      (node (ref "U1") (pin "D13") (pinfunction "IO_L33N_0_D13") (pintype "bidirectional"))
    )
    (net (code "415") (name "/XP2C_22") (class "Default")
      (node (ref "U1") (pin "C15") (pinfunction "IO_L37P_GCLK13_0_C15") (pintype "bidirectional"))
    )
    (net (code "416") (name "/XP2C_23") (class "Default")
      (node (ref "U1") (pin "J15") (pinfunction "IO_L51P_0_J15") (pintype "bidirectional"))
    )
    (net (code "417") (name "/XP2C_24") (class "Default")
      (node (ref "U1") (pin "H15") (pinfunction "IO_L51N_0_H15") (pintype "bidirectional"))
    )
    (net (code "418") (name "/XP2C_30") (class "Default")
      (node (ref "U1") (pin "E20") (pinfunction "IO_L58P_0_E20") (pintype "bidirectional"))
    )
    (net (code "419") (name "/XP2C_37") (class "Default")
      (node (ref "U1") (pin "E19") (pinfunction "IO_L54P_0_E19") (pintype "bidirectional"))
    )
    (net (code "420") (name "/XP2C_38") (class "Default")
      (node (ref "U1") (pin "D23") (pinfunction "IO_L3P_M5RESET_5_D23") (pintype "bidirectional"))
    )
    (net (code "422") (name "/XP2D_3") (class "Default")
      (node (ref "U1") (pin "E5") (pinfunction "IO_L80N_M4A12_4_E5") (pintype "bidirectional"))
    )
    (net (code "423") (name "/XP2D_4") (class "Default")
      (node (ref "U1") (pin "D5") (pinfunction "IO_L3N_0_D5") (pintype "bidirectional"))
    )
    (net (code "424") (name "/XP2D_10") (class "Default")
      (node (ref "U1") (pin "E6") (pinfunction "IO_L3P_0_E6") (pintype "bidirectional"))
    )
    (net (code "425") (name "/XP2D_11") (class "Default")
      (node (ref "U1") (pin "D6") (pinfunction "IO_L8P_0_D6") (pintype "bidirectional"))
    )
    (net (code "426") (name "/XP2D_12") (class "Default")
      (node (ref "U1") (pin "D8") (pinfunction "IO_L14P_0_D8") (pintype "bidirectional"))
    )
    (net (code "427") (name "/XP2D_13") (class "Default")
      (node (ref "U1") (pin "E8") (pinfunction "IO_L13P_0_E8") (pintype "bidirectional"))
    )
    (net (code "428") (name "/XP2D_14") (class "Default")
      (node (ref "U1") (pin "E9") (pinfunction "IO_L15N_0_E9") (pintype "bidirectional"))
    )
    (net (code "429") (name "/XP2D_15") (class "Default")
      (node (ref "U1") (pin "E10") (pinfunction "IO_L18P_0_E10") (pintype "bidirectional"))
    )
    (net (code "430") (name "/XP2D_16") (class "Default")
      (node (ref "U1") (pin "F11") (pinfunction "IO_L23N_0_F11") (pintype "bidirectional"))
    )
    (net (code "431") (name "/XP2D_17") (class "Default")
      (node (ref "U1") (pin "D12") (pinfunction "IO_L31P_0_D12") (pintype "bidirectional+no_connect"))
    )
    (net (code "432") (name "/XP2D_18") (class "Default")
      (node (ref "U1") (pin "D15") (pinfunction "IO_L44N_0_D15") (pintype "bidirectional"))
    )
    (net (code "433") (name "/XP2D_23") (class "Default")
      (node (ref "U1") (pin "B16") (pinfunction "IO_L38P_0_B16") (pintype "bidirectional"))
    )
    (net (code "434") (name "/XP2D_24") (class "Default")
      (node (ref "U1") (pin "C17") (pinfunction "IO_L50P_0_C17") (pintype "bidirectional"))
    )
    (net (code "435") (name "/XP2D_37") (class "Default")
      (node (ref "U1") (pin "D21") (pinfunction "IO_L56P_0_D21") (pintype "bidirectional"))
    )
    (net (code "436") (name "/XP2D_38") (class "Default")
      (node (ref "U1") (pin "B24") (pinfunction "IO_L10P_M5A0_5_B24") (pintype "bidirectional"))
    )
    (net (code "438") (name "/XP3A_3") (class "Default")
      (node (ref "U1") (pin "V10") (pinfunction "IO_L21N_3_V10") (pintype "bidirectional"))
    )
    (net (code "439") (name "/XP3A_4") (class "Default")
      (node (ref "U1") (pin "U9") (pinfunction "IO_L25N_3_U9") (pintype "bidirectional"))
    )
    (net (code "440") (name "/XP3A_5") (class "Default")
      (node (ref "U1") (pin "V5") (pinfunction "IO_L24N_3_V5") (pintype "bidirectional"))
    )
    (net (code "441") (name "/XP3A_6") (class "Default")
      (node (ref "U1") (pin "W7") (pinfunction "IO_L15N_3_W7") (pintype "bidirectional"))
    )
    (net (code "442") (name "/XP3A_7") (class "Default")
      (node (ref "U1") (pin "Y6") (pinfunction "IO_L7N_3_Y6") (pintype "bidirectional"))
    )
    (net (code "443") (name "/XP3A_8") (class "Default")
      (node (ref "U1") (pin "AA5") (pinfunction "IO_L16P_3_AA5") (pintype "bidirectional"))
    )
    (net (code "444") (name "/XP3A_9") (class "Default")
      (node (ref "U1") (pin "AA8") (pinfunction "IO_L4P_3_AA8") (pintype "bidirectional"))
    )
    (net (code "445") (name "/XP3A_10") (class "Default")
      (node (ref "U1") (pin "Y9") (pinfunction "IO_L9P_3_Y9") (pintype "bidirectional"))
    )
    (net (code "446") (name "/XP3A_11") (class "Default")
      (node (ref "U1") (pin "Y10") (pinfunction "IO_L51P_2_Y10") (pintype "bidirectional"))
    )
    (net (code "447") (name "/XP3A_12") (class "Default")
      (node (ref "U1") (pin "Y5") (pinfunction "IO_L22N_3_Y5") (pintype "bidirectional"))
    )
    (net (code "448") (name "/XP3A_13") (class "Default")
      (node (ref "U1") (pin "AD5") (pinfunction "IO_L10N_3_AD5") (pintype "bidirectional"))
    )
    (net (code "449") (name "/XP3A_14") (class "Default")
      (node (ref "U1") (pin "W12") (pinfunction "IO_L46N_2_W12") (pintype "bidirectional"))
    )
    (net (code "450") (name "/XP3A_15") (class "Default")
      (node (ref "U1") (pin "AB11") (pinfunction "IO_L43N_2_AB11") (pintype "bidirectional"))
    )
    (net (code "451") (name "/XP3A_16") (class "Default")
      (node (ref "U1") (pin "AC9") (pinfunction "IO_L58P_2_AC9") (pintype "bidirectional"))
    )
    (net (code "452") (name "/XP3A_17") (class "Default")
      (node (ref "U1") (pin "Y13") (pinfunction "IO_L33N_2_Y13") (pintype "bidirectional"))
    )
    (net (code "453") (name "/XP3A_18") (class "Default")
      (node (ref "U1") (pin "AC11") (pinfunction "IO_L45P_2_AC11") (pintype "bidirectional"))
    )
    (net (code "454") (name "/XP3A_20") (class "Default")
      (node (ref "U1") (pin "AB13") (pinfunction "IO_L34N_2_AB13") (pintype "bidirectional"))
    )
    (net (code "455") (name "/XP3A_21") (class "Default")
      (node (ref "U1") (pin "AA13") (pinfunction "IO_L34P_2_AA13") (pintype "bidirectional"))
    )
    (net (code "456") (name "/XP3A_23") (class "Default")
      (node (ref "U1") (pin "Y14") (pinfunction "IO_L28P_2_Y14") (pintype "bidirectional"))
    )
    (net (code "457") (name "/XP3A_24") (class "Default")
      (node (ref "U1") (pin "AC14") (pinfunction "IO_L19N_2_AC14") (pintype "bidirectional"))
    )
    (net (code "458") (name "/XP3A_25") (class "Default")
      (node (ref "U1") (pin "T10") (pinfunction "IO_L25P_3_T10") (pintype "bidirectional"))
    )
    (net (code "459") (name "/XP3A_26") (class "Default")
      (node (ref "U1") (pin "V8") (pinfunction "IO_L19N_3_V8") (pintype "bidirectional"))
    )
    (net (code "460") (name "/XP3A_27") (class "Default")
      (node (ref "U1") (pin "U23") (pinfunction "IO_L59N_1_U23") (pintype "bidirectional"))
    )
    (net (code "461") (name "/XP3A_28") (class "Default")
      (node (ref "U1") (pin "AC13") (pinfunction "IO_L31P_GCLK31_D14_2_AC13") (pintype "bidirectional"))
    )
    (net (code "462") (name "/XP3A_29") (class "Default")
      (node (ref "U1") (pin "P17") (pinfunction "IO_L56P_1_P17") (pintype "bidirectional"))
    )
    (net (code "463") (name "/XP3A_30") (class "Default")
      (node (ref "U1") (pin "P18") (pinfunction "IO_L56N_1_P18") (pintype "bidirectional"))
    )
    (net (code "464") (name "/XP3A_31") (class "Default")
      (node (ref "U1") (pin "Y8") (pinfunction "IO_L9N_3_Y8") (pintype "bidirectional"))
    )
    (net (code "465") (name "/XP3A_32") (class "Default")
      (node (ref "U1") (pin "W9") (pinfunction "IO_L19P_3_W9") (pintype "bidirectional"))
    )
    (net (code "466") (name "/XP3A_33") (class "Default")
      (node (ref "U1") (pin "W10") (pinfunction "IO_L21P_3_W10") (pintype "bidirectional"))
    )
    (net (code "467") (name "/XP3A_34") (class "Default")
      (node (ref "U1") (pin "R17") (pinfunction "IO_L58P_1_R17") (pintype "bidirectional"))
    )
    (net (code "468") (name "/XP3A_35") (class "Default")
      (node (ref "U1") (pin "V12") (pinfunction "IO_L46P_2_V12") (pintype "bidirectional"))
    )
    (net (code "469") (name "/XP3A_36") (class "Default")
      (node (ref "U1") (pin "W13") (pinfunction "IO_L33P_2_W13") (pintype "bidirectional"))
    )
    (net (code "470") (name "/XP3A_37") (class "Default")
      (node (ref "U1") (pin "AB15") (pinfunction "IO_L19P_2_AB15") (pintype "bidirectional"))
    )
    (net (code "471") (name "/XP3A_38") (class "Default")
      (node (ref "U1") (pin "M21") (pinfunction "IO_L40N_GCLK10_M1A6_1_M21") (pintype "bidirectional"))
    )
    (net (code "473") (name "/XP3B_3") (class "Default")
      (node (ref "U1") (pin "AB1") (pinfunction "IO_L32N_M3DQ15_3_AB1") (pintype "bidirectional"))
    )
    (net (code "474") (name "/XP3B_4") (class "Default")
      (node (ref "U1") (pin "V6") (pinfunction "IO_L17N_VREF_3_V6") (pintype "bidirectional"))
    )
    (net (code "475") (name "/XP3B_5") (class "Default")
      (node (ref "U1") (pin "W5") (pinfunction "IO_L22P_3_W5") (pintype "bidirectional"))
    )
    (net (code "476") (name "/XP3B_6") (class "Default")
      (node (ref "U1") (pin "AB4") (pinfunction "IO_L18P_3_AB4") (pintype "bidirectional"))
    )
    (net (code "477") (name "/XP3B_7") (class "Default")
      (node (ref "U1") (pin "AB5") (pinfunction "IO_L16N_3_AB5") (pintype "bidirectional"))
    )
    (net (code "478") (name "/XP3B_8") (class "Default")
      (node (ref "U1") (pin "AB7") (pinfunction "IO_L8P_3_AB7") (pintype "bidirectional"))
    )
    (net (code "479") (name "/XP3B_9") (class "Default")
      (node (ref "U1") (pin "AA7") (pinfunction "IO_L7P_3_AA7") (pintype "bidirectional"))
    )
    (net (code "480") (name "/XP3B_10") (class "Default")
      (node (ref "U1") (pin "AB9") (pinfunction "IO_L61N_VREF_2_AB9") (pintype "bidirectional"))
    )
    (net (code "481") (name "/XP3B_11") (class "Default")
      (node (ref "U1") (pin "W11") (pinfunction "IO_L52N_2_W11") (pintype "bidirectional"))
    )
    (net (code "482") (name "/XP3B_12") (class "Default")
      (node (ref "U1") (pin "AA9") (pinfunction "IO_L61P_2_AA9") (pintype "bidirectional"))
    )
    (net (code "483") (name "/XP3B_13") (class "Default")
      (node (ref "U1") (pin "AB6") (pinfunction "IO_L8N_3_AB6") (pintype "bidirectional"))
    )
    (net (code "484") (name "/XP3B_14") (class "Default")
      (node (ref "U1") (pin "AA11") (pinfunction "IO_L43P_2_AA11") (pintype "bidirectional"))
    )
    (net (code "485") (name "/XP3B_15") (class "Default")
      (node (ref "U1") (pin "AB8") (pinfunction "IO_L4N_3_AB8") (pintype "bidirectional"))
    )
    (net (code "486") (name "/XP3B_16") (class "Default")
      (node (ref "U1") (pin "AD11") (pinfunction "IO_L45N_2_AD11") (pintype "bidirectional"))
    )
    (net (code "487") (name "/XP3B_17") (class "Default")
      (node (ref "U1") (pin "V13") (pinfunction "IO_L44P_2_V13") (pintype "bidirectional"))
    )
    (net (code "488") (name "/XP3B_18") (class "Default")
      (node (ref "U1") (pin "AD9") (pinfunction "IO_L58N_2_AD9") (pintype "bidirectional"))
    )
    (net (code "489") (name "/XP3B_19") (class "Default")
      (node (ref "U1") (pin "AC12") (pinfunction "IO_L41N_VREF_2_AC12") (pintype "bidirectional"))
    )
    (net (code "490") (name "/XP3B_22") (class "Default")
      (node (ref "U1") (pin "U12") (pinfunction "IO_L50N_2_U12") (pintype "bidirectional"))
    )
    (net (code "491") (name "/XP3B_23") (class "Default")
      (node (ref "U1") (pin "U13") (pinfunction "IO_L50P_2_U13") (pintype "bidirectional"))
    )
    (net (code "492") (name "/XP3B_24") (class "Default")
      (node (ref "U1") (pin "V7") (pinfunction "IO_L17P_3_V7") (pintype "bidirectional"))
    )
    (net (code "493") (name "/XP3B_25") (class "Default")
      (node (ref "U1") (pin "W14") (pinfunction "IO_L44N_2_W14") (pintype "bidirectional"))
    )
    (net (code "494") (name "/XP3B_26") (class "Default")
      (node (ref "U1") (pin "V18") (pinfunction "IO_L66P_1_V18") (pintype "bidirectional"))
    )
    (net (code "495") (name "/XP3B_27") (class "Default")
      (node (ref "U1") (pin "W19") (pinfunction "IO_L68N_1_W19") (pintype "bidirectional"))
    )
    (net (code "496") (name "/XP3B_28") (class "Default")
      (node (ref "U1") (pin "AB22") (pinfunction "IO_L69N_VREF_1_AB22") (pintype "bidirectional"))
    )
    (net (code "497") (name "/XP3B_29") (class "Default")
      (node (ref "U1") (pin "AA23") (pinfunction "IO_L63P_1_AA23") (pintype "bidirectional"))
    )
    (net (code "498") (name "/XP3B_30") (class "Default")
      (node (ref "U1") (pin "AA14") (pinfunction "IO_L28N_2_AA14") (pintype "bidirectional"))
    )
    (net (code "499") (name "/XP3B_31") (class "Default")
      (node (ref "U1") (pin "V22") (pinfunction "IO_L71P_1_V22") (pintype "bidirectional"))
    )
    (net (code "500") (name "/XP3B_32") (class "Default")
      (node (ref "U1") (pin "Y15") (pinfunction "IO_L20P_2_Y15") (pintype "bidirectional"))
    )
    (net (code "501") (name "/XP3B_33") (class "Default")
      (node (ref "U1") (pin "V11") (pinfunction "IO_L52P_2_V11") (pintype "bidirectional"))
    )
    (net (code "502") (name "/XP3B_34") (class "Default")
      (node (ref "U1") (pin "V19") (pinfunction "IO_L66N_1_V19") (pintype "bidirectional"))
    )
    (net (code "503") (name "/XP3B_35") (class "Default")
      (node (ref "U1") (pin "R19") (pinfunction "IO_L57N_1_R19") (pintype "bidirectional"))
    )
    (net (code "504") (name "/XP3B_36") (class "Default")
      (node (ref "U1") (pin "L20") (pinfunction "IO_L26P_5_L20") (pintype "bidirectional"))
    )
    (net (code "505") (name "/XP3B_37") (class "Default")
      (node (ref "U1") (pin "AA24") (pinfunction "IO_L63N_1_AA24") (pintype "bidirectional"))
    )
    (net (code "506") (name "/XP3B_38") (class "Default")
      (node (ref "U1") (pin "V23") (pinfunction "IO_L42P_GCLK7_M1UDM_1_V23") (pintype "bidirectional"))
    )
    (net (code "508") (name "/XP3C_3") (class "Default")
      (node (ref "U1") (pin "AB3") (pinfunction "IO_L32P_M3DQ14_3_AB3") (pintype "bidirectional"))
    )
    (net (code "509") (name "/XP3C_4") (class "Default")
      (node (ref "U1") (pin "Y3") (pinfunction "IO_L37P_M3DQ0_3_Y3") (pintype "bidirectional"))
    )
    (net (code "510") (name "/XP3C_5") (class "Default")
      (node (ref "U1") (pin "U5") (pinfunction "IO_L24P_3_U5") (pintype "bidirectional"))
    )
    (net (code "511") (name "/XP3C_6") (class "Default")
      (node (ref "U1") (pin "AA4") (pinfunction "IO_L20P_3_AA4") (pintype "bidirectional"))
    )
    (net (code "512") (name "/XP3C_7") (class "Default")
      (node (ref "U1") (pin "AC3") (pinfunction "IO_L18N_3_AC3") (pintype "bidirectional"))
    )
    (net (code "513") (name "/XP3C_8") (class "Default")
      (node (ref "U1") (pin "AC5") (pinfunction "IO_L10P_3_AC5") (pintype "bidirectional"))
    )
    (net (code "514") (name "/XP3C_9") (class "Default")
      (node (ref "U1") (pin "AC2") (pinfunction "IO_L34P_M3UDQS_3_AC2") (pintype "bidirectional"))
    )
    (net (code "515") (name "/XP3C_10") (class "Default")
      (node (ref "U1") (pin "AD3") (pinfunction "IO_L33P_M3DQ12_3_AD3") (pintype "bidirectional"))
    )
    (net (code "516") (name "/XP3C_11") (class "Default")
      (node (ref "U1") (pin "AD4") (pinfunction "IO_L3N_3_AD4") (pintype "bidirectional"))
    )
    (net (code "517") (name "/XP3C_12") (class "Default")
      (node (ref "U1") (pin "AB10") (pinfunction "IO_L51N_2_AB10") (pintype "bidirectional"))
    )
    (net (code "518") (name "/XP3C_13") (class "Default")
      (node (ref "U1") (pin "AC7") (pinfunction "IO_L1P_3_AC7") (pintype "bidirectional"))
    )
    (net (code "519") (name "/XP3C_14") (class "Default")
      (node (ref "U1") (pin "AD6") (pinfunction "IO_L63P_2_AD6") (pintype "bidirectional"))
    )
    (net (code "520") (name "/XP3C_15") (class "Default")
      (node (ref "U1") (pin "AD7") (pinfunction "IO_L1N_VREF_3_AD7") (pintype "bidirectional"))
    )
    (net (code "521") (name "/XP3C_16") (class "Default")
      (node (ref "U1") (pin "AD8") (pinfunction "IO_L53P_2_AD8") (pintype "bidirectional"))
    )
    (net (code "522") (name "/XP3C_19") (class "Default")
      (node (ref "U1") (pin "AD12") (pinfunction "IO_L32P_GCLK29_2_AD12") (pintype "bidirectional"))
    )
    (net (code "523") (name "/XP3C_22") (class "Default")
      (node (ref "U1") (pin "U7") (pinfunction "IO_L23N_3_U7") (pintype "bidirectional"))
    )
    (net (code "524") (name "/XP3C_25") (class "Default")
      (node (ref "U1") (pin "J17") (pinfunction "IO_L59P_0_J17") (pintype "bidirectional"))
    )
    (net (code "525") (name "/XP3C_26") (class "Default")
      (node (ref "U1") (pin "V14") (pinfunction "IO_L42N_2_V14") (pintype "bidirectional"))
    )
    (net (code "526") (name "/XP3C_27") (class "Default")
      (node (ref "U1") (pin "AA15") (pinfunction "IO_L20N_2_AA15") (pintype "bidirectional"))
    )
    (net (code "527") (name "/XP3C_28") (class "Default")
      (node (ref "U1") (pin "AA12") (pinfunction "IO_L41P_2_AA12") (pintype "bidirectional"))
    )
    (net (code "528") (name "/XP3C_29") (class "Default")
      (node (ref "U1") (pin "Y22") (pinfunction "IO_L73P_1_Y22") (pintype "bidirectional"))
    )
    (net (code "529") (name "/XP3C_30") (class "Default")
      (node (ref "U1") (pin "R18") (pinfunction "IO_L58N_1_R18") (pintype "bidirectional"))
    )
    (net (code "530") (name "/XP3C_31") (class "Default")
      (node (ref "U1") (pin "W18") (pinfunction "IO_L68P_1_W18") (pintype "bidirectional"))
    )
    (net (code "531") (name "/XP3C_32") (class "Default")
      (node (ref "U1") (pin "AB21") (pinfunction "IO_L69P_1_AB21") (pintype "bidirectional"))
    )
    (net (code "532") (name "/XP3C_33") (class "Default")
      (node (ref "U1") (pin "U21") (pinfunction "IO_L61P_1_U21") (pintype "bidirectional"))
    )
    (net (code "533") (name "/XP3C_34") (class "Default")
      (node (ref "U1") (pin "V17") (pinfunction "IO_L62N_1_V17") (pintype "bidirectional"))
    )
    (net (code "534") (name "/XP3C_35") (class "Default")
      (node (ref "U1") (pin "U22") (pinfunction "IO_L61N_1_U22") (pintype "bidirectional"))
    )
    (net (code "535") (name "/XP3C_36") (class "Default")
      (node (ref "U1") (pin "AC24") (pinfunction "IO_L65N_1_AC24") (pintype "bidirectional"))
    )
    (net (code "536") (name "/XP3C_37") (class "Default")
      (node (ref "U1") (pin "AB24") (pinfunction "IO_L49P_M1DQ10_1_AB24") (pintype "bidirectional"))
    )
    (net (code "537") (name "/XP3C_38") (class "Default")
      (node (ref "U1") (pin "W24") (pinfunction "IO_L42N_GCLK6_TRDY1_M1LDM_1_W24") (pintype "bidirectional"))
    )
    (net (code "539") (name "/XP3D_3") (class "Default")
      (node (ref "U1") (pin "AC1") (pinfunction "IO_L34N_M3UDQSN_3_AC1") (pintype "bidirectional"))
    )
    (net (code "540") (name "/XP3D_4") (class "Default")
      (node (ref "U1") (pin "AD1") (pinfunction "IO_L33N_M3DQ13_3_AD1") (pintype "bidirectional"))
    )
    (net (code "541") (name "/XP3D_5") (class "Default")
      (node (ref "U1") (pin "AE1") (pinfunction "IO_L35N_M3DQ11_3_AE1") (pintype "bidirectional"))
    )
    (net (code "542") (name "/XP3D_6") (class "Default")
      (node (ref "U1") (pin "AE2") (pinfunction "IO_L35P_M3DQ10_3_AE2") (pintype "bidirectional"))
    )
    (net (code "543") (name "/XP3D_7") (class "Default")
      (node (ref "U1") (pin "AF2") (pinfunction "IO_L2N_3_AF2") (pintype "bidirectional"))
    )
    (net (code "544") (name "/XP3D_8") (class "Default")
      (node (ref "U1") (pin "AE5") (pinfunction "IO_L64P_D8_2_AE5") (pintype "bidirectional"))
    )
    (net (code "545") (name "/XP3D_9") (class "Default")
      (node (ref "U1") (pin "AC4") (pinfunction "IO_L3P_3_AC4") (pintype "bidirectional"))
    )
    (net (code "546") (name "/XP3D_10") (class "Default")
      (node (ref "U1") (pin "AE3") (pinfunction "IO_L2P_3_AE3") (pintype "bidirectional"))
    )
    (net (code "547") (name "/XP3D_11") (class "Default")
      (node (ref "U1") (pin "AF5") (pinfunction "IO_L64N_D9_2_AF5") (pintype "bidirectional"))
    )
    (net (code "548") (name "/XP3D_12") (class "Default")
      (node (ref "U1") (pin "AF6") (pinfunction "IO_L63N_2_AF6") (pintype "bidirectional"))
    )
    (net (code "549") (name "/XP3D_13") (class "Default")
      (node (ref "U1") (pin "AF8") (pinfunction "IO_L53N_2_AF8") (pintype "bidirectional"))
    )
    (net (code "550") (name "/XP3D_14") (class "Default")
      (node (ref "U1") (pin "AE11") (pinfunction "IO_L47P_2_AE11") (pintype "bidirectional"))
    )
    (net (code "551") (name "/XP3D_15") (class "Default")
      (node (ref "U1") (pin "AF11") (pinfunction "IO_L47N_2_AF11") (pintype "bidirectional"))
    )
    (net (code "552") (name "/XP3D_16") (class "Default")
      (node (ref "U1") (pin "AF12") (pinfunction "IO_L32N_GCLK28_2_AF12") (pintype "bidirectional"))
    )
    (net (code "553") (name "/XP3D_19") (class "Default")
      (node (ref "U1") (pin "AD13") (pinfunction "IO_L31N_GCLK30_D15_2_AD13") (pintype "bidirectional"))
    )
    (net (code "554") (name "/XP3D_25") (class "Default")
      (node (ref "U1") (pin "U15") (pinfunction "IO_L42P_2_U15") (pintype "bidirectional"))
    )
    (net (code "555") (name "/XP3D_26") (class "Default")
      (node (ref "U1") (pin "AF16") (pinfunction "IO_L13N_D10_2_AF16") (pintype "bidirectional"))
    )
    (net (code "556") (name "/XP3D_27") (class "Default")
      (node (ref "U1") (pin "V20") (pinfunction "IO_L70N_1_V20") (pintype "bidirectional"))
    )
    (net (code "557") (name "/XP3D_28") (class "Default")
      (node (ref "U1") (pin "AC23") (pinfunction "IO_L65P_1_AC23") (pintype "bidirectional"))
    )
    (net (code "558") (name "/XP3D_29") (class "Default")
      (node (ref "U1") (pin "Y20") (pinfunction "IO_L72P_1_Y20") (pintype "bidirectional"))
    )
    (net (code "559") (name "/XP3D_30") (class "Default")
      (node (ref "U1") (pin "AE24") (pinfunction "IO_L67P_1_AE24") (pintype "bidirectional"))
    )
    (net (code "560") (name "/XP3D_31") (class "Default")
      (node (ref "U1") (pin "AF25") (pinfunction "IO_L67N_1_AF25") (pintype "bidirectional"))
    )
    (net (code "561") (name "/XP3D_32") (class "Default")
      (node (ref "U1") (pin "T19") (pinfunction "IO_L60N_1_T19") (pintype "bidirectional"))
    )
    (net (code "562") (name "/XP3D_33") (class "Default")
      (node (ref "U1") (pin "AE25") (pinfunction "IO_L52P_M1DQ14_1_AE25") (pintype "bidirectional"))
    )
    (net (code "563") (name "/XP3D_34") (class "Default")
      (node (ref "U1") (pin "AE26") (pinfunction "IO_L52N_M1DQ15_1_AE26") (pintype "bidirectional"))
    )
    (net (code "564") (name "/XP3D_35") (class "Default")
      (node (ref "U1") (pin "AD26") (pinfunction "IO_L48N_M1DQ9_1_AD26") (pintype "bidirectional"))
    )
    (net (code "565") (name "/XP3D_36") (class "Default")
      (node (ref "U1") (pin "AC25") (pinfunction "IO_L50P_M1UDQS_1_AC25") (pintype "bidirectional"))
    )
    (net (code "566") (name "/XP3D_37") (class "Default")
      (node (ref "U1") (pin "AC26") (pinfunction "IO_L50N_M1UDQSN_1_AC26") (pintype "bidirectional"))
    )
    (net (code "567") (name "/XP3D_38") (class "Default")
      (node (ref "U1") (pin "AB26") (pinfunction "IO_L49N_M1DQ11_1_AB26") (pintype "bidirectional"))
    )
    (net (code "569") (name "/XP4A_3") (class "Default")
      (node (ref "U1") (pin "H16") (pinfunction "IO_L55P_0_H16") (pintype "bidirectional"))
    )
    (net (code "570") (name "/XP4A_4") (class "Default")
      (node (ref "U1") (pin "J20") (pinfunction "IO_L27N_5_J20") (pintype "bidirectional"))
    )
    (net (code "571") (name "/XP4A_5") (class "Default")
      (node (ref "U1") (pin "B26") (pinfunction "IO_L12N_M5ODT_5_B26") (pintype "bidirectional"))
    )
    (net (code "572") (name "/XP4A_6") (class "Default")
      (node (ref "U1") (pin "C26") (pinfunction "IO_L11N_M5CLKN_5_C26") (pintype "bidirectional"))
    )
    (net (code "573") (name "/XP4A_7") (class "Default")
      (node (ref "U1") (pin "D26") (pinfunction "IO_L17N_M5DQ7_5_D26") (pintype "bidirectional"))
    )
    (net (code "574") (name "/XP4A_8") (class "Default")
      (node (ref "U1") (pin "E26") (pinfunction "IO_L16N_M5DQ5_5_E26") (pintype "bidirectional"))
    )
    (net (code "575") (name "/XP4A_9") (class "Default")
      (node (ref "U1") (pin "F26") (pinfunction "IO_L18N_M5LDQSN_5_F26") (pintype "bidirectional"))
    )
    (net (code "576") (name "/XP4A_29") (class "Default")
      (node (ref "U1") (pin "K26") (pinfunction "IO_L21N_M5DQ9_5_K26") (pintype "bidirectional"))
    )
    (net (code "577") (name "/XP4A_30") (class "Default")
      (node (ref "U1") (pin "L26") (pinfunction "IO_L24N_M5DQ13_5_L26") (pintype "bidirectional"))
    )
    (net (code "578") (name "/XP4A_31") (class "Default")
      (node (ref "U1") (pin "M26") (pinfunction "IO_L23N_M5UDQSN_5_M26") (pintype "bidirectional"))
    )
    (net (code "579") (name "/XP4A_32") (class "Default")
      (node (ref "U1") (pin "N25") (pinfunction "IO_L25P_M5DQ14_5_N25") (pintype "bidirectional"))
    )
    (net (code "580") (name "/XP4A_33") (class "Default")
      (node (ref "U1") (pin "N26") (pinfunction "IO_L25N_M5DQ15_5_N26") (pintype "bidirectional"))
    )
    (net (code "581") (name "/XP4A_34") (class "Default")
      (node (ref "U1") (pin "U26") (pinfunction "IO_L43N_GCLK4_M1DQ5_1_U26") (pintype "bidirectional"))
    )
    (net (code "582") (name "/XP4A_35") (class "Default")
      (node (ref "U1") (pin "U25") (pinfunction "IO_L43P_GCLK5_M1DQ4_1_U25") (pintype "bidirectional"))
    )
    (net (code "583") (name "/XP4A_36") (class "Default")
      (node (ref "U1") (pin "Y26") (pinfunction "IO_L47N_LDC_M1DQ1_1_Y26") (pintype "bidirectional"))
    )
    (net (code "584") (name "/XP4A_37") (class "Default")
      (node (ref "U1") (pin "AA26") (pinfunction "IO_L51N_M1DQ13_1_AA26") (pintype "bidirectional"))
    )
    (net (code "585") (name "/XP4A_38") (class "Default")
      (node (ref "U1") (pin "AA25") (pinfunction "IO_L51P_M1DQ12_1_AA25") (pintype "bidirectional"))
    )
    (net (code "587") (name "/XP4B_3") (class "Default")
      (node (ref "U1") (pin "J24") (pinfunction "IO_L15N_M5LDM_5_J24") (pintype "bidirectional"))
    )
    (net (code "588") (name "/XP4B_4") (class "Default")
      (node (ref "U1") (pin "K19") (pinfunction "IO_L28N_VREF_1_K19") (pintype "bidirectional"))
    )
    (net (code "589") (name "/XP4B_5") (class "Default")
      (node (ref "U1") (pin "C25") (pinfunction "IO_L11P_M5CLK_5_C25") (pintype "bidirectional"))
    )
    (net (code "590") (name "/XP4B_6") (class "Default")
      (node (ref "U1") (pin "C24") (pinfunction "IO_L3N_M5A11_5_C24") (pintype "bidirectional"))
    )
    (net (code "591") (name "/XP4B_7") (class "Default")
      (node (ref "U1") (pin "E25") (pinfunction "IO_L16P_M5DQ4_5_E25") (pintype "bidirectional"))
    )
    (net (code "592") (name "/XP4B_8") (class "Default")
      (node (ref "U1") (pin "F24") (pinfunction "IO_L18P_M5LDQS_5_F24") (pintype "bidirectional"))
    )
    (net (code "593") (name "/XP4B_29") (class "Default")
      (node (ref "U1") (pin "N20") (pinfunction "IO_L40P_GCLK11_M1A5_1_N20") (pintype "bidirectional"))
    )
    (net (code "594") (name "/XP4B_30") (class "Default")
      (node (ref "U1") (pin "P21") (pinfunction "IO_L41P_GCLK9_IRDY1_M1RASN_1_P21") (pintype "bidirectional"))
    )
    (net (code "595") (name "/XP4B_31") (class "Default")
      (node (ref "U1") (pin "P22") (pinfunction "IO_L41N_GCLK8_M1CASN_1_P22") (pintype "bidirectional"))
    )
    (net (code "596") (name "/XP4B_32") (class "Default")
      (node (ref "U1") (pin "R22") (pinfunction "IO_L55P_1_R22") (pintype "bidirectional"))
    )
    (net (code "597") (name "/XP4B_33") (class "Default")
      (node (ref "U1") (pin "R24") (pinfunction "IO_L39N_M1ODT_1_R24") (pintype "bidirectional"))
    )
    (net (code "598") (name "/XP4B_34") (class "Default")
      (node (ref "U1") (pin "R20") (pinfunction "IO_L57P_1_R20") (pintype "bidirectional"))
    )
    (net (code "599") (name "/XP4B_35") (class "Default")
      (node (ref "U1") (pin "T22") (pinfunction "IO_L59P_1_T22") (pintype "bidirectional"))
    )
    (net (code "600") (name "/XP4B_36") (class "Default")
      (node (ref "U1") (pin "U24") (pinfunction "IO_L53N_VREF_1_U24") (pintype "bidirectional"))
    )
    (net (code "601") (name "/XP4B_37") (class "Default")
      (node (ref "U1") (pin "T18") (pinfunction "IO_L60P_1_T18") (pintype "bidirectional"))
    )
    (net (code "602") (name "/XP4B_38") (class "Default")
      (node (ref "U1") (pin "T23") (pinfunction "IO_L53P_1_T23") (pintype "bidirectional"))
    )
    (net (code "604") (name "/XP4C_3") (class "Default")
      (node (ref "U1") (pin "D22") (pinfunction "IO_L4N_M5A12_5_D22") (pintype "bidirectional"))
    )
    (net (code "605") (name "/XP4C_4") (class "Default")
      (node (ref "U1") (pin "E23") (pinfunction "IO_L7P_M5WE_5_E23") (pintype "bidirectional"))
    )
    (net (code "606") (name "/XP4C_5") (class "Default")
      (node (ref "U1") (pin "G20") (pinfunction "IO_L2P_M5A13_5_G20") (pintype "bidirectional"))
    )
    (net (code "607") (name "/XP4C_6") (class "Default")
      (node (ref "U1") (pin "G21") (pinfunction "IO_L2N_M5A14_5_G21") (pintype "bidirectional"))
    )
    (net (code "608") (name "/XP4C_7") (class "Default")
      (node (ref "U1") (pin "E24") (pinfunction "IO_L7N_M5BA2_5_E24") (pintype "bidirectional"))
    )
    (net (code "609") (name "/XP4C_8") (class "Default")
      (node (ref "U1") (pin "H24") (pinfunction "IO_L19P_M5DQ2_5_H24") (pintype "bidirectional"))
    )
    (net (code "610") (name "/XP4C_29") (class "Default")
      (node (ref "U1") (pin "H26") (pinfunction "IO_L19N_M5DQ3_5_H26") (pintype "bidirectional"))
    )
    (net (code "611") (name "/XP4C_30") (class "Default")
      (node (ref "U1") (pin "J26") (pinfunction "IO_L22N_M5DQ11_5_J26") (pintype "bidirectional"))
    )
    (net (code "612") (name "/XP4C_31") (class "Default")
      (node (ref "U1") (pin "P10") (pinfunction "IO_L49P_M3A7_3_P10") (pintype "bidirectional"))
    )
    (net (code "613") (name "/XP4C_32") (class "Default")
      (node (ref "U1") (pin "J23") (pinfunction "IO_L15P_M5UDM_5_J23") (pintype "bidirectional"))
    )
    (net (code "614") (name "/XP4C_33") (class "Default")
      (node (ref "U1") (pin "R23") (pinfunction "IO_L39P_M1A3_1_R23") (pintype "bidirectional"))
    )
    (net (code "615") (name "/XP4C_34") (class "Default")
      (node (ref "U1") (pin "H21") (pinfunction "IO_L5N_M5A9_5_H21") (pintype "bidirectional"))
    )
    (net (code "616") (name "/XP4C_35") (class "Default")
      (node (ref "U1") (pin "H20") (pinfunction "IO_L5P_M5A8_5_H20") (pintype "bidirectional"))
    )
    (net (code "617") (name "/XP4C_36") (class "Default")
      (node (ref "U1") (pin "L21") (pinfunction "IO_L26N_VREF_5_L21") (pintype "bidirectional"))
    )
    (net (code "618") (name "/XP4C_37") (class "Default")
      (node (ref "U1") (pin "R21") (pinfunction "IO_L55N_1_R21") (pintype "bidirectional"))
    )
    (net (code "619") (name "/XP4C_38") (class "Default")
      (node (ref "U1") (pin "AD24") (pinfunction "IO_L48P_HDC_M1DQ8_1_AD24") (pintype "bidirectional"))
    )
    (net (code "621") (name "/XP4D_3") (class "Default")
      (node (ref "U1") (pin "G23") (pinfunction "IO_L8P_M5A7_5_G23") (pintype "bidirectional"))
    )
    (net (code "622") (name "/XP4D_4") (class "Default")
      (node (ref "U1") (pin "D24") (pinfunction "IO_L17P_M5DQ6_5_D24") (pintype "bidirectional"))
    )
    (net (code "623") (name "/XP4D_5") (class "Default")
      (node (ref "U1") (pin "F22") (pinfunction "IO_L4P_M5CKE_5_F22") (pintype "bidirectional"))
    )
    (net (code "624") (name "/XP4D_6") (class "Default")
      (node (ref "U1") (pin "G22") (pinfunction "IO_L6N_M5A4_5_G22") (pintype "bidirectional"))
    )
    (net (code "625") (name "/XP4D_7") (class "Default")
      (node (ref "U1") (pin "G24") (pinfunction "IO_L8N_M5A2_5_G24") (pintype "bidirectional"))
    )
    (net (code "626") (name "/XP4D_8") (class "Default")
      (node (ref "U1") (pin "J25") (pinfunction "IO_L22P_M5DQ10_5_J25") (pintype "bidirectional"))
    )
    (net (code "627") (name "/XP4D_22") (class "Default")
      (node (ref "U1") (pin "G26") (pinfunction "IO_L20N_M5DQ1_5_G26") (pintype "bidirectional"))
    )
    (net (code "628") (name "/XP4D_23") (class "Default")
      (node (ref "U1") (pin "G25") (pinfunction "IO_L20P_M5DQ0_5_G25") (pintype "bidirectional"))
    )
    (net (code "629") (name "/XP4D_29") (class "Default")
      (node (ref "U1") (pin "L19") (pinfunction "IO_L28P_1_L19") (pintype "bidirectional"))
    )
    (net (code "630") (name "/XP4D_30") (class "Default")
      (node (ref "U1") (pin "N9") (pinfunction "IO_L51N_M3A4_3_N9") (pintype "bidirectional"))
    )
    (net (code "631") (name "/XP4D_31") (class "Default")
      (node (ref "U1") (pin "H22") (pinfunction "IO_L6P_M5A10_5_H22") (pintype "bidirectional"))
    )
    (net (code "632") (name "/XP4D_32") (class "Default")
      (node (ref "U1") (pin "H19") (pinfunction "IO_L27P_5_H19") (pintype "bidirectional"))
    )
    (net (code "633") (name "/XP4D_33") (class "Default")
      (node (ref "U1") (pin "G19") (pinfunction "IO_L9N_M5BA1_5_G19") (pintype "bidirectional"))
    )
    (net (code "634") (name "/XP4D_34") (class "Default")
      (node (ref "U1") (pin "K24") (pinfunction "IO_L21P_M5DQ8_5_K24") (pintype "bidirectional"))
    )
    (net (code "635") (name "/XP4D_35") (class "Default")
      (node (ref "U1") (pin "K20") (pinfunction "IO_L13P_M5A5_5_K20") (pintype "bidirectional"))
    )
    (net (code "636") (name "/XP4D_36") (class "Default")
      (node (ref "U1") (pin "J22") (pinfunction "IO_L14N_M5CASN_5_J22") (pintype "bidirectional"))
    )
    (net (code "637") (name "/XP4D_37") (class "Default")
      (node (ref "U1") (pin "K22") (pinfunction "IO_L14P_M5RASN_5_K22") (pintype "bidirectional"))
    )
    (net (code "638") (name "/XP4D_38") (class "Default")
      (node (ref "U1") (pin "T20") (pinfunction "IO_L64P_1_T20") (pintype "bidirectional"))
    )
    (net (code "639") (name "/a0") (class "Default")
      (node (ref "U1") (pin "V26") (pinfunction "IO_L45N_A0_M1LDQSN_1_V26") (pintype "bidirectional+no_connect"))
    )
    (net (code "640") (name "/a1") (class "Default")
      (node (ref "U1") (pin "V24") (pinfunction "IO_L45P_A1_M1LDQS_1_V24") (pintype "bidirectional+no_connect"))
    )
    (net (code "641") (name "/a2") (class "Default")
      (node (ref "U1") (pin "W26") (pinfunction "IO_L44N_A2_M1DQ7_1_W26") (pintype "bidirectional+no_connect"))
    )
    (net (code "642") (name "/a3") (class "Default")
      (node (ref "U1") (pin "W25") (pinfunction "IO_L44P_A3_M1DQ6_1_W25") (pintype "bidirectional+no_connect"))
    )
    (net (code "643") (name "/a4") (class "Default")
      (node (ref "U1") (pin "N18") (pinfunction "IO_L38N_A4_M1CLKN_1_N18") (pintype "bidirectional+no_connect"))
    )
    (net (code "644") (name "/a5") (class "Default")
      (node (ref "U1") (pin "N17") (pinfunction "IO_L38P_A5_M1CLK_1_N17") (pintype "bidirectional+no_connect"))
    )
    (net (code "645") (name "/a6") (class "Default")
      (node (ref "U1") (pin "N23") (pinfunction "IO_L37N_A6_M1A1_1_N23") (pintype "bidirectional+no_connect"))
    )
    (net (code "646") (name "/a7") (class "Default")
      (node (ref "U1") (pin "N22") (pinfunction "IO_L37P_A7_M1A0_1_N22") (pintype "bidirectional+no_connect"))
    )
    (net (code "647") (name "/a8") (class "Default")
      (node (ref "U1") (pin "N19") (pinfunction "IO_L36N_A8_M1BA1_1_N19") (pintype "bidirectional+no_connect"))
    )
    (net (code "648") (name "/a9") (class "Default")
      (node (ref "U1") (pin "M18") (pinfunction "IO_L36P_A9_M1BA0_1_M18") (pintype "bidirectional+no_connect"))
    )
    (net (code "649") (name "/a10") (class "Default")
      (node (ref "U1") (pin "R26") (pinfunction "IO_L35N_A10_M1A2_1_R26") (pintype "bidirectional+no_connect"))
    )
    (net (code "650") (name "/a11") (class "Default")
      (node (ref "U1") (pin "R25") (pinfunction "IO_L35P_A11_M1A7_1_R25") (pintype "bidirectional+no_connect"))
    )
    (net (code "651") (name "/a12") (class "Default")
      (node (ref "U1") (pin "L18") (pinfunction "IO_L34N_A12_M1BA2_1_L18") (pintype "bidirectional+no_connect"))
    )
    (net (code "652") (name "/a13") (class "Default")
      (node (ref "U1") (pin "M19") (pinfunction "IO_L34P_A13_M1WE_1_M19") (pintype "bidirectional+no_connect"))
    )
    (net (code "653") (name "/a14") (class "Default")
      (node (ref "U1") (pin "P26") (pinfunction "IO_L33N_A14_M1A4_1_P26") (pintype "bidirectional+no_connect"))
    )
    (net (code "654") (name "/a15") (class "Default")
      (node (ref "U1") (pin "P24") (pinfunction "IO_L33P_A15_M1A10_1_P24") (pintype "bidirectional+no_connect"))
    )
    (net (code "655") (name "/a16") (class "Default")
      (node (ref "U1") (pin "K18") (pinfunction "IO_L32N_A16_M1A9_1_K18") (pintype "bidirectional+no_connect"))
    )
    (net (code "656") (name "/a17") (class "Default")
      (node (ref "U1") (pin "L17") (pinfunction "IO_L32P_A17_M1A8_1_L17") (pintype "bidirectional+no_connect"))
    )
    (net (code "657") (name "/a18") (class "Default")
      (node (ref "U1") (pin "N24") (pinfunction "IO_L31N_A18_M1A12_1_N24") (pintype "bidirectional+no_connect"))
    )
    (net (code "658") (name "/a19") (class "Default")
      (node (ref "U1") (pin "M23") (pinfunction "IO_L31P_A19_M1CKE_1_M23") (pintype "bidirectional+no_connect"))
    )
    (net (code "659") (name "/a20") (class "Default")
      (node (ref "U1") (pin "N21") (pinfunction "IO_L30N_A20_M1A11_1_N21") (pintype "bidirectional+no_connect"))
    )
    (net (code "660") (name "/a21") (class "Default")
      (node (ref "U1") (pin "P20") (pinfunction "IO_L30P_A21_M1RESET_1_P20") (pintype "bidirectional+no_connect"))
    )
    (net (code "661") (name "/a22") (class "Default")
      (node (ref "U1") (pin "L24") (pinfunction "IO_L29N_A22_M1A14_1_L24") (pintype "bidirectional+no_connect"))
    )
    (net (code "662") (name "/a23") (class "Default")
      (node (ref "U1") (pin "L23") (pinfunction "IO_L29P_A23_M1A13_1_L23") (pintype "bidirectional+no_connect"))
    )
    (net (code "663") (name "/adc_eoc") (class "Default")
      (node (ref "U1") (pin "A20") (pinfunction "IO_L64N_SCP4_0_A20") (pintype "bidirectional"))
    )
    (net (code "664") (name "/adc_ncs") (class "Default")
      (node (ref "U1") (pin "B22") (pinfunction "IO_L66P_SCP1_0_B22") (pintype "bidirectional"))
    )
    (net (code "665") (name "/adc_sck") (class "Default")
      (node (ref "U1") (pin "A21") (pinfunction "IO_L65N_SCP2_0_A21") (pintype "bidirectional"))
    )
    (net (code "666") (name "/adc_sdi") (class "Default")
      (node (ref "U1") (pin "C21") (pinfunction "IO_L65P_SCP3_0_C21") (pintype "bidirectional"))
    )
    (net (code "667") (name "/adc_sdo") (class "Default")
      (node (ref "U1") (pin "A22") (pinfunction "IO_L66N_SCP0_0_A22") (pintype "bidirectional"))
    )
    (net (code "668") (name "/dout_busy") (class "Default")
      (node (ref "U1") (pin "AF24") (pinfunction "IO_L74N_DOUT_BUSY_1_AF24") (pintype "bidirectional+no_connect"))
    )
    (net (code "669") (name "/elink0_n") (class "Default")
      (node (ref "U1") (pin "AA19") (pinfunction "IO_L6N_2_AA19") (pintype "bidirectional"))
    )
    (net (code "670") (name "/elink0_p") (class "Default")
      (node (ref "U1") (pin "Y18") (pinfunction "IO_L6P_2_Y18") (pintype "bidirectional"))
    )
    (net (code "671") (name "/elink1_n") (class "Default")
      (node (ref "U1") (pin "AF18") (pinfunction "IO_L9N_2_AF18") (pintype "bidirectional"))
    )
    (net (code "672") (name "/elink1_p") (class "Default")
      (node (ref "U1") (pin "AD18") (pinfunction "IO_L9P_2_AD18") (pintype "bidirectional"))
    )
    (net (code "673") (name "/elink2_n") (class "Default")
      (node (ref "U1") (pin "AD17") (pinfunction "IO_L17N_2_AD17") (pintype "bidirectional"))
    )
    (net (code "674") (name "/elink2_p") (class "Default")
      (node (ref "U1") (pin "AC16") (pinfunction "IO_L17P_2_AC16") (pintype "bidirectional"))
    )
    (net (code "675") (name "/elink3_n") (class "Default")
      (node (ref "U1") (pin "AF15") (pinfunction "IO_L14N_D12_2_AF15") (pintype "bidirectional"))
    )
    (net (code "676") (name "/elink3_p") (class "Default")
      (node (ref "U1") (pin "AE15") (pinfunction "IO_L14P_D11_2_AE15") (pintype "bidirectional"))
    )
    (net (code "677") (name "/elink4_n") (class "Default")
      (node (ref "U1") (pin "AD19") (pinfunction "IO_L7N_2_AD19") (pintype "bidirectional"))
    )
    (net (code "678") (name "/elink4_p") (class "Default")
      (node (ref "U1") (pin "AC19") (pinfunction "IO_L7P_2_AC19") (pintype "bidirectional"))
    )
    (net (code "679") (name "/elink5_n") (class "Default")
      (node (ref "U1") (pin "AF19") (pinfunction "IO_L4N_VREF_2_AF19") (pintype "bidirectional"))
    )
    (net (code "680") (name "/elink5_p") (class "Default")
      (node (ref "U1") (pin "AE19") (pinfunction "IO_L4P_2_AE19") (pintype "bidirectional"))
    )
    (net (code "681") (name "/elink6_n") (class "Default")
      (node (ref "U1") (pin "W16") (pinfunction "IO_L18N_2_W16") (pintype "bidirectional"))
    )
    (net (code "682") (name "/elink6_p") (class "Default")
      (node (ref "U1") (pin "V15") (pinfunction "IO_L18P_2_V15") (pintype "bidirectional"))
    )
    (net (code "683") (name "/elink7_n") (class "Default")
      (node (ref "U1") (pin "AA17") (pinfunction "IO_L10N_2_AA17") (pintype "bidirectional"))
    )
    (net (code "684") (name "/elink7_p") (class "Default")
      (node (ref "U1") (pin "Y16") (pinfunction "IO_L10P_2_Y16") (pintype "bidirectional"))
    )
    (net (code "685") (name "/elink8_n") (class "Default")
      (node (ref "U1") (pin "AD15") (pinfunction "IO_L16N_VREF_2_AD15") (pintype "bidirectional"))
    )
    (net (code "686") (name "/elink8_p") (class "Default")
      (node (ref "U1") (pin "AC15") (pinfunction "IO_L16P_2_AC15") (pintype "bidirectional"))
    )
    (net (code "687") (name "/elink9_n") (class "Default")
      (node (ref "U1") (pin "AF21") (pinfunction "IO_L2N_CMPMOSI_2_AF21") (pintype "bidirectional"))
    )
    (net (code "688") (name "/elink9_p") (class "Default")
      (node (ref "U1") (pin "AE21") (pinfunction "IO_L2P_CMPCLK_2_AE21") (pintype "bidirectional"))
    )
    (net (code "689") (name "/elink10_n") (class "Default")
      (node (ref "U1") (pin "AB18") (pinfunction "IO_L11N_2_AB18") (pintype "bidirectional"))
    )
    (net (code "690") (name "/elink10_p") (class "Default")
      (node (ref "U1") (pin "AA18") (pinfunction "IO_L11P_2_AA18") (pintype "bidirectional"))
    )
    (net (code "691") (name "/elink11_n") (class "Default")
      (node (ref "U1") (pin "W17") (pinfunction "IO_L8N_2_W17") (pintype "bidirectional"))
    )
    (net (code "692") (name "/elink11_p") (class "Default")
      (node (ref "U1") (pin "V16") (pinfunction "IO_L8P_2_V16") (pintype "bidirectional"))
    )
    (net (code "693") (name "/elink12_n") (class "Default")
      (node (ref "U1") (pin "AD21") (pinfunction "IO_L5N_2_AD21") (pintype "bidirectional"))
    )
    (net (code "694") (name "/elink12_p") (class "Default")
      (node (ref "U1") (pin "AC20") (pinfunction "IO_L5P_2_AC20") (pintype "bidirectional"))
    )
    (net (code "695") (name "/elink13_n") (class "Default")
      (node (ref "U1") (pin "AC17") (pinfunction "IO_L15N_2_AC17") (pintype "bidirectional"))
    )
    (net (code "696") (name "/elink13_p") (class "Default")
      (node (ref "U1") (pin "AB17") (pinfunction "IO_L15P_2_AB17") (pintype "bidirectional"))
    )
    (net (code "697") (name "/en_2v5_sfp_xfpga") (class "Default")
      (node (ref "U1") (pin "W8") (pinfunction "IO_L15P_3_W8") (pintype "bidirectional+no_connect"))
    )
    (net (code "698") (name "/fcs") (class "Default")
      (node (ref "U1") (pin "T24") (pinfunction "IO_L46P_FCS_B_M1DQ2_1_T24") (pintype "bidirectional+no_connect"))
    )
    (net (code "699") (name "/foe") (class "Default")
      (node (ref "U1") (pin "T26") (pinfunction "IO_L46N_FOE_B_M1DQ3_1_T26") (pintype "bidirectional+no_connect"))
    )
    (net (code "700") (name "/fwe") (class "Default")
      (node (ref "U1") (pin "Y24") (pinfunction "IO_L47P_FWE_B_M1DQ0_1_Y24") (pintype "bidirectional+no_connect"))
    )
    (net (code "701") (name "/gbt_clk40_n") (class "Default")
      (node (ref "U1") (pin "AF14") (pinfunction "IO_L29N_GCLK2_2_AF14") (pintype "bidirectional"))
    )
    (net (code "702") (name "/gbt_clk40_p") (class "Default")
      (node (ref "U1") (pin "AD14") (pinfunction "IO_L29P_GCLK3_2_AD14") (pintype "bidirectional"))
    )
    (net (code "703") (name "/gbt_clk320_n") (class "Default")
      (node (ref "U1") (pin "AF13") (pinfunction "IO_L30N_GCLK0_USERCCLK_2_AF13") (pintype "bidirectional"))
    )
    (net (code "704") (name "/gbt_clk320_p") (class "Default")
      (node (ref "U1") (pin "AE13") (pinfunction "IO_L30P_GCLK1_D13_2_AE13") (pintype "bidirectional"))
    )
    (net (code "705") (name "/gbt_tx_datavalid") (class "Default")
      (node (ref "U1") (pin "M24") (pinfunction "IO_L23P_M5UDQS_5_M24") (pintype "bidirectional"))
    )
    (net (code "706") (name "/gbt_txrdy") (class "Default")
      (node (ref "U1") (pin "K21") (pinfunction "IO_L13N_M5A6_5_K21") (pintype "bidirectional"))
    )
    (net (code "707") (name "/gbt_widebus") (class "Default")
      (node (ref "U39") (pin "4") (pinfunction "Y_4") (pintype "open_collector"))
    )
    (net (code "708") (name "/gbt_widebus_3v3") (class "Default")
      (node (ref "R98") (pin "2") (pinfunction "2_2") (pintype "passive"))
      (node (ref "U1") (pin "L25") (pinfunction "IO_L24P_M5DQ12_5_L25") (pintype "bidirectional"))
      (node (ref "U39") (pin "2") (pinfunction "A_2") (pintype "input"))
      (node (ref "U43") (pin "2") (pinfunction "A_2") (pintype "input"))
    )
    (net (code "709") (name "/gbt_~{reset}_ex") (class "Default")
      (node (ref "U1") (pin "U8") (pinfunction "IO_L23P_3_U8") (pintype "bidirectional+no_connect"))
    )
    (net (code "710") (name "/led1") (class "Default")
      (node (ref "U1") (pin "A18") (pinfunction "IO_L62N_VREF_0_A18") (pintype "bidirectional"))
    )
    (net (code "711") (name "/led2") (class "Default")
      (node (ref "U1") (pin "A19") (pinfunction "IO_L63N_SCP6_0_A19") (pintype "bidirectional"))
    )
    (net (code "712") (name "/led3") (class "Default")
      (node (ref "U1") (pin "D20") (pinfunction "IO_L58N_0_D20") (pintype "bidirectional"))
    )
    (net (code "713") (name "/led4") (class "Default")
      (node (ref "U1") (pin "G17") (pinfunction "IO_L55N_0_G17") (pintype "bidirectional"))
    )
    (net (code "714") (name "/led5") (class "Default")
      (node (ref "U1") (pin "C18") (pinfunction "IO_L52N_0_C18") (pintype "bidirectional"))
    )
    (net (code "715") (name "/led6") (class "Default")
      (node (ref "U1") (pin "D18") (pinfunction "IO_L52P_0_D18") (pintype "bidirectional"))
    )
    (net (code "716") (name "/led7") (class "Default")
      (node (ref "U1") (pin "D19") (pinfunction "IO_L54N_0_D19") (pintype "bidirectional"))
    )
    (net (code "717") (name "/led8") (class "Default")
      (node (ref "U1") (pin "F16") (pinfunction "IO_L49P_0_F16") (pintype "bidirectional"))
    )
    (net (code "718") (name "/led9") (class "Default")
      (node (ref "U1") (pin "E17") (pinfunction "IO_L48N_0_E17") (pintype "bidirectional"))
    )
    (net (code "719") (name "/led10") (class "Default")
      (node (ref "U1") (pin "E18") (pinfunction "IO_L57N_0_E18") (pintype "bidirectional"))
    )
    (net (code "720") (name "/led11") (class "Default")
      (node (ref "U1") (pin "E14") (pinfunction "IO_L44P_0_E14") (pintype "bidirectional"))
    )
    (net (code "721") (name "/led12") (class "Default")
      (node (ref "U1") (pin "F15") (pinfunction "IO_L47N_0_F15") (pintype "bidirectional"))
    )
    (net (code "722") (name "/led13") (class "Default")
      (node (ref "U1") (pin "F17") (pinfunction "IO_L48P_0_F17") (pintype "bidirectional"))
    )
    (net (code "723") (name "/led14") (class "Default")
      (node (ref "U1") (pin "E16") (pinfunction "IO_L49N_0_E16") (pintype "bidirectional"))
    )
    (net (code "724") (name "/led15") (class "Default")
      (node (ref "U1") (pin "C20") (pinfunction "IO_L56N_0_C20") (pintype "bidirectional"))
    )
    (net (code "725") (name "/led16") (class "Default")
      (node (ref "U1") (pin "B18") (pinfunction "IO_L62P_0_B18") (pintype "bidirectional"))
    )
    (net (code "726") (name "/led17") (class "Default")
      (node (ref "U1") (pin "C19") (pinfunction "IO_L63P_SCP7_0_C19") (pintype "bidirectional"))
    )
    (net (code "727") (name "/led18") (class "Default")
      (node (ref "U1") (pin "H17") (pinfunction "IO_L59N_0_H17") (pintype "bidirectional"))
    )
    (net (code "728") (name "/led19") (class "Default")
      (node (ref "U1") (pin "H18") (pinfunction "IO_L9P_M5BA0_5_H18") (pintype "bidirectional"))
    )
    (net (code "729") (name "/led20") (class "Default")
      (node (ref "U1") (pin "F18") (pinfunction "IO_L57P_0_F18") (pintype "bidirectional"))
    )
    (net (code "731") (name "/mc_sn") (class "Default")
      (node (ref "U1") (pin "B14") (pinfunction "IO_L35P_GCLK17_0_B14") (pintype "bidirectional"))
    )
    (net (code "732") (name "/mez_clock") (class "Default")
      (node (ref "R91") (pin "2") (pinfunction "2_2") (pintype "passive"))
      (node (ref "R92") (pin "1") (pinfunction "1_1") (pintype "passive"))
      (node (ref "U1") (pin "A14") (pinfunction "IO_L35N_GCLK16_0_A14") (pintype "bidirectional"))
    )
    (net (code "733") (name "/unused1") (class "Default")
      (node (ref "U1") (pin "Y21") (pinfunction "IO_L72N_1_Y21") (pintype "bidirectional+no_connect"))
    )
    (net (code "734") (name "/unused2") (class "Default")
      (node (ref "U1") (pin "AA22") (pinfunction "IO_L73N_1_AA22") (pintype "bidirectional+no_connect"))
    )
    (net (code "735") (name "/unused5") (class "Default")
      (node (ref "U1") (pin "R10") (pinfunction "IO_L27P_3_R10") (pintype "bidirectional+no_connect"))
    )
    (net (code "736") (name "/unused6") (class "Default")
      (node (ref "U1") (pin "T9") (pinfunction "IO_L27N_3_T9") (pintype "bidirectional+no_connect"))
    )
    (net (code "737") (name "/unused7") (class "Default")
      (node (ref "U1") (pin "T8") (pinfunction "IO_L29P_3_T8") (pintype "bidirectional+no_connect"))
    )
    (net (code "738") (name "/unused8") (class "Default")
      (node (ref "U1") (pin "R7") (pinfunction "IO_L31P_3_R7") (pintype "bidirectional"))
    )
    (net (code "739") (name "/unused9") (class "Default")
      (node (ref "U1") (pin "R6") (pinfunction "IO_L31N_VREF_3_R6") (pintype "bidirectional"))
    )
    (net (code "740") (name "/unused10") (class "Default")
      (node (ref "U1") (pin "P8") (pinfunction "IO_L43N_GCLK22_IRDY2_M3CASN_3_P8") (pintype "bidirectional"))
    )
    (net (code "741") (name "/unused11") (class "Default")
      (node (ref "U1") (pin "R9") (pinfunction "IO_L49N_M3A2_3_R9") (pintype "bidirectional"))
    )
    (net (code "742") (name "/unused12") (class "Default")
      (node (ref "U1") (pin "M10") (pinfunction "IO_L51P_M3A10_3_M10") (pintype "bidirectional"))
    )
    (net (code "743") (name "/unused13") (class "Default")
      (node (ref "U1") (pin "M9") (pinfunction "IO_L53P_M3CKE_3_M9") (pintype "bidirectional"))
    )
    (net (code "744") (name "/unused14") (class "Default")
      (node (ref "U1") (pin "M8") (pinfunction "IO_L53N_M3A12_3_M8") (pintype "bidirectional"))
    )
    (net (code "745") (name "/unused15") (class "Default")
      (node (ref "U1") (pin "L4") (pinfunction "IO_L54P_M3RESET_3_L4") (pintype "bidirectional"))
    )
    (net (code "746") (name "/unused16") (class "Default")
      (node (ref "U1") (pin "M6") (pinfunction "IO_L55P_M3A13_3_M6") (pintype "bidirectional+no_connect"))
    )
    (net (code "747") (name "/unused17") (class "Default")
      (node (ref "U1") (pin "L7") (pinfunction "IO_L57P_3_L7") (pintype "bidirectional+no_connect"))
    )
    (net (code "748") (name "/unused18") (class "Default")
      (node (ref "U1") (pin "L6") (pinfunction "IO_L57N_VREF_3_L6") (pintype "bidirectional+no_connect"))
    )
    (net (code "749") (name "/unused19") (class "Default")
      (node (ref "U1") (pin "K8") (pinfunction "IO_L58P_4_K8") (pintype "bidirectional"))
    )
    (net (code "750") (name "/unused20") (class "Default")
      (node (ref "U1") (pin "L8") (pinfunction "IO_L58N_VREF_4_L8") (pintype "bidirectional"))
    )
    (net (code "751") (name "/unused21") (class "Default")
      (node (ref "U1") (pin "N2") (pinfunction "IO_L59P_M4DQ14_4_N2") (pintype "bidirectional"))
    )
    (net (code "752") (name "/unused22") (class "Default")
      (node (ref "U1") (pin "K7") (pinfunction "IO_L70P_M4RASN_4_K7") (pintype "bidirectional"))
    )
    (net (code "753") (name "/unused23") (class "Default")
      (node (ref "U1") (pin "K6") (pinfunction "IO_L70N_M4CASN_4_K6") (pintype "bidirectional+no_connect"))
    )
    (net (code "754") (name "/unused24") (class "Default")
      (node (ref "U1") (pin "J7") (pinfunction "IO_L72P_M4A3_4_J7") (pintype "bidirectional+no_connect"))
    )
    (net (code "755") (name "/unused25") (class "Default")
      (node (ref "U1") (pin "H7") (pinfunction "IO_L72N_M4ODT_4_H7") (pintype "bidirectional+no_connect"))
    )
    (net (code "756") (name "/unused26") (class "Default")
      (node (ref "U1") (pin "K10") (pinfunction "IO_L74P_M4A0_4_K10") (pintype "bidirectional+no_connect"))
    )
    (net (code "757") (name "/unused27") (class "Default")
      (node (ref "U1") (pin "L9") (pinfunction "IO_L74N_M4A1_4_L9") (pintype "bidirectional+no_connect"))
    )
    (net (code "758") (name "/unused28") (class "Default")
      (node (ref "U1") (pin "H6") (pinfunction "IO_L75P_M4BA0_4_H6") (pintype "bidirectional+no_connect"))
    )
    (net (code "759") (name "/unused29") (class "Default")
      (node (ref "U1") (pin "J10") (pinfunction "IO_L76P_M4A7_4_J10") (pintype "bidirectional+no_connect"))
    )
    (net (code "760") (name "/unused30") (class "Default")
      (node (ref "U1") (pin "K9") (pinfunction "IO_L76N_M4A2_4_K9") (pintype "bidirectional+no_connect"))
    )
    (net (code "761") (name "/unused31") (class "Default")
      (node (ref "U1") (pin "G6") (pinfunction "IO_L78P_M4A10_4_G6") (pintype "bidirectional+no_connect"))
    )
    (net (code "762") (name "/unused32") (class "Default")
      (node (ref "U1") (pin "G5") (pinfunction "IO_L78N_M4A4_4_G5") (pintype "bidirectional+no_connect"))
    )
    (net (code "763") (name "/unused33") (class "Default")
      (node (ref "U1") (pin "H8") (pinfunction "IO_L82P_M4A13_4_H8") (pintype "bidirectional+no_connect"))
    )
    (net (code "764") (name "/unused34") (class "Default")
      (node (ref "U1") (pin "G7") (pinfunction "IO_L82N_M4A14_4_G7") (pintype "bidirectional+no_connect"))
    )
    (net (code "765") (name "/unused35") (class "Default")
      (node (ref "U1") (pin "G8") (pinfunction "IO_L5P_0_G8") (pintype "bidirectional+no_connect"))
    )
    (net (code "766") (name "/unused36") (class "Default")
      (node (ref "U1") (pin "F7") (pinfunction "IO_L5N_0_F7") (pintype "bidirectional+no_connect"))
    )
    (net (code "767") (name "/unused37") (class "Default")
      (node (ref "U1") (pin "F9") (pinfunction "IO_L15P_0_F9") (pintype "bidirectional+no_connect"))
    )
    (net (code "768") (name "/unused38") (class "Default")
      (node (ref "U1") (pin "J14") (pinfunction "IO_L43P_0_J14") (pintype "bidirectional+no_connect"))
    )
    (net (code "769") (name "/unused39") (class "Default")
      (node (ref "U1") (pin "G16") (pinfunction "IO_L47P_0_G16") (pintype "bidirectional+no_connect"))
    )
    (net (code "770") (name "/unused40") (class "Default")
      (node (ref "U1") (pin "W22") (pinfunction "IO_L71N_1_W22") (pintype "bidirectional"))
    )
    (net (code "772") (name "GND") (class "Default")
      (node (ref "D9") (pin "K") (pinfunction "CATHODE_K") (pintype "passive"))
      (node (ref "R92") (pin "2") (pinfunction "2_2") (pintype "passive"))
      (node (ref "U43") (pin "3") (pinfunction "GND_3") (pintype "power_in"))
    )
    (net (code "773") (name "Net-(D9-ANODE)") (class "Default")
      (node (ref "D9") (pin "A") (pinfunction "ANODE_A") (pintype "passive"))
      (node (ref "R111") (pin "2") (pinfunction "2_2") (pintype "passive"))
    )
    (net (code "774") (name "Net-(U43A-Y)") (class "Default")
      (node (ref "R111") (pin "1") (pinfunction "1_1") (pintype "passive"))
      (node (ref "U43") (pin "4") (pinfunction "Y_4") (pintype "open_collector"))
    )
    (net (code "775") (name "unconnected-(U1B-IO_L62P_1-PadU17)") (class "Default")
      (node (ref "U1") (pin "U17") (pinfunction "IO_L62P_1_U17") (pintype "bidirectional+no_connect"))
    )
    (net (code "776") (name "unconnected-(U1B-IO_L64N_1-PadU20)") (class "Default")
      (node (ref "U1") (pin "U20") (pinfunction "IO_L64N_1_U20") (pintype "bidirectional+no_connect"))
    )
    (net (code "777") (name "unconnected-(U1B-IO_L70P_1-PadU19)") (class "Default")
      (node (ref "U1") (pin "U19") (pinfunction "IO_L70P_1_U19") (pintype "bidirectional+no_connect"))
    )
    (net (code "778") (name "unconnected-(U1C-IO_L65N_CSO_B_2-PadAF4)") (class "Default")
      (node (ref "U1") (pin "AF4") (pinfunction "IO_L65N_CSO_B_2_AF4") (pintype "bidirectional+no_connect"))
    )
    (net (code "779") (name "unconnected-(U43B-NC-Pad1)") (class "Default")
      (node (ref "U43") (pin "1") (pinfunction "NC_1") (pintype "passive"))
    )
  )
)
